# swift-nav.net
KiCad netlist of a schematic drawn in EAGLE
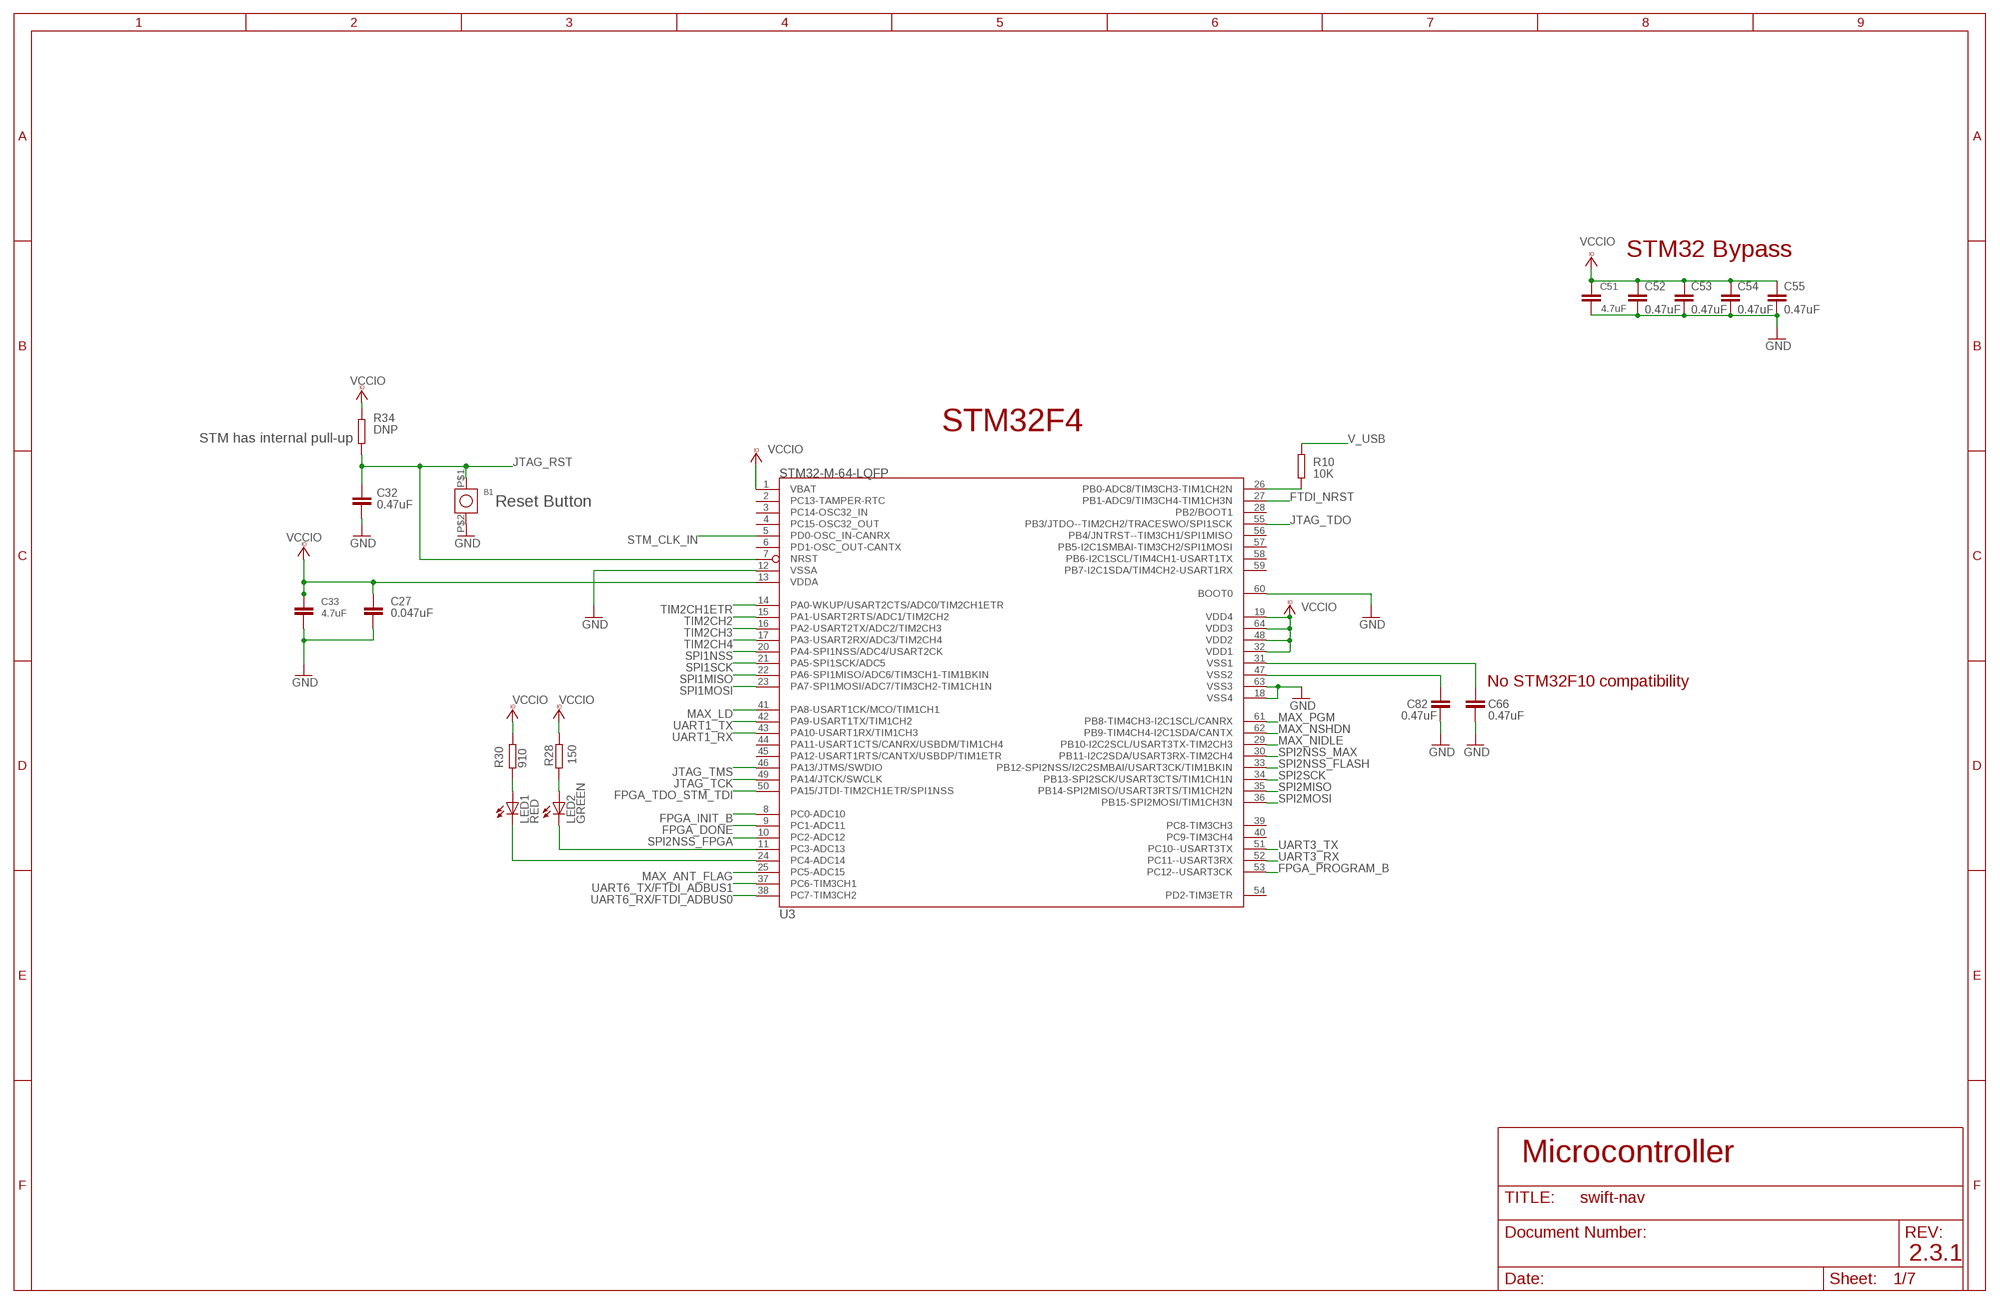
[diagram p0: schematic, sheet 1]
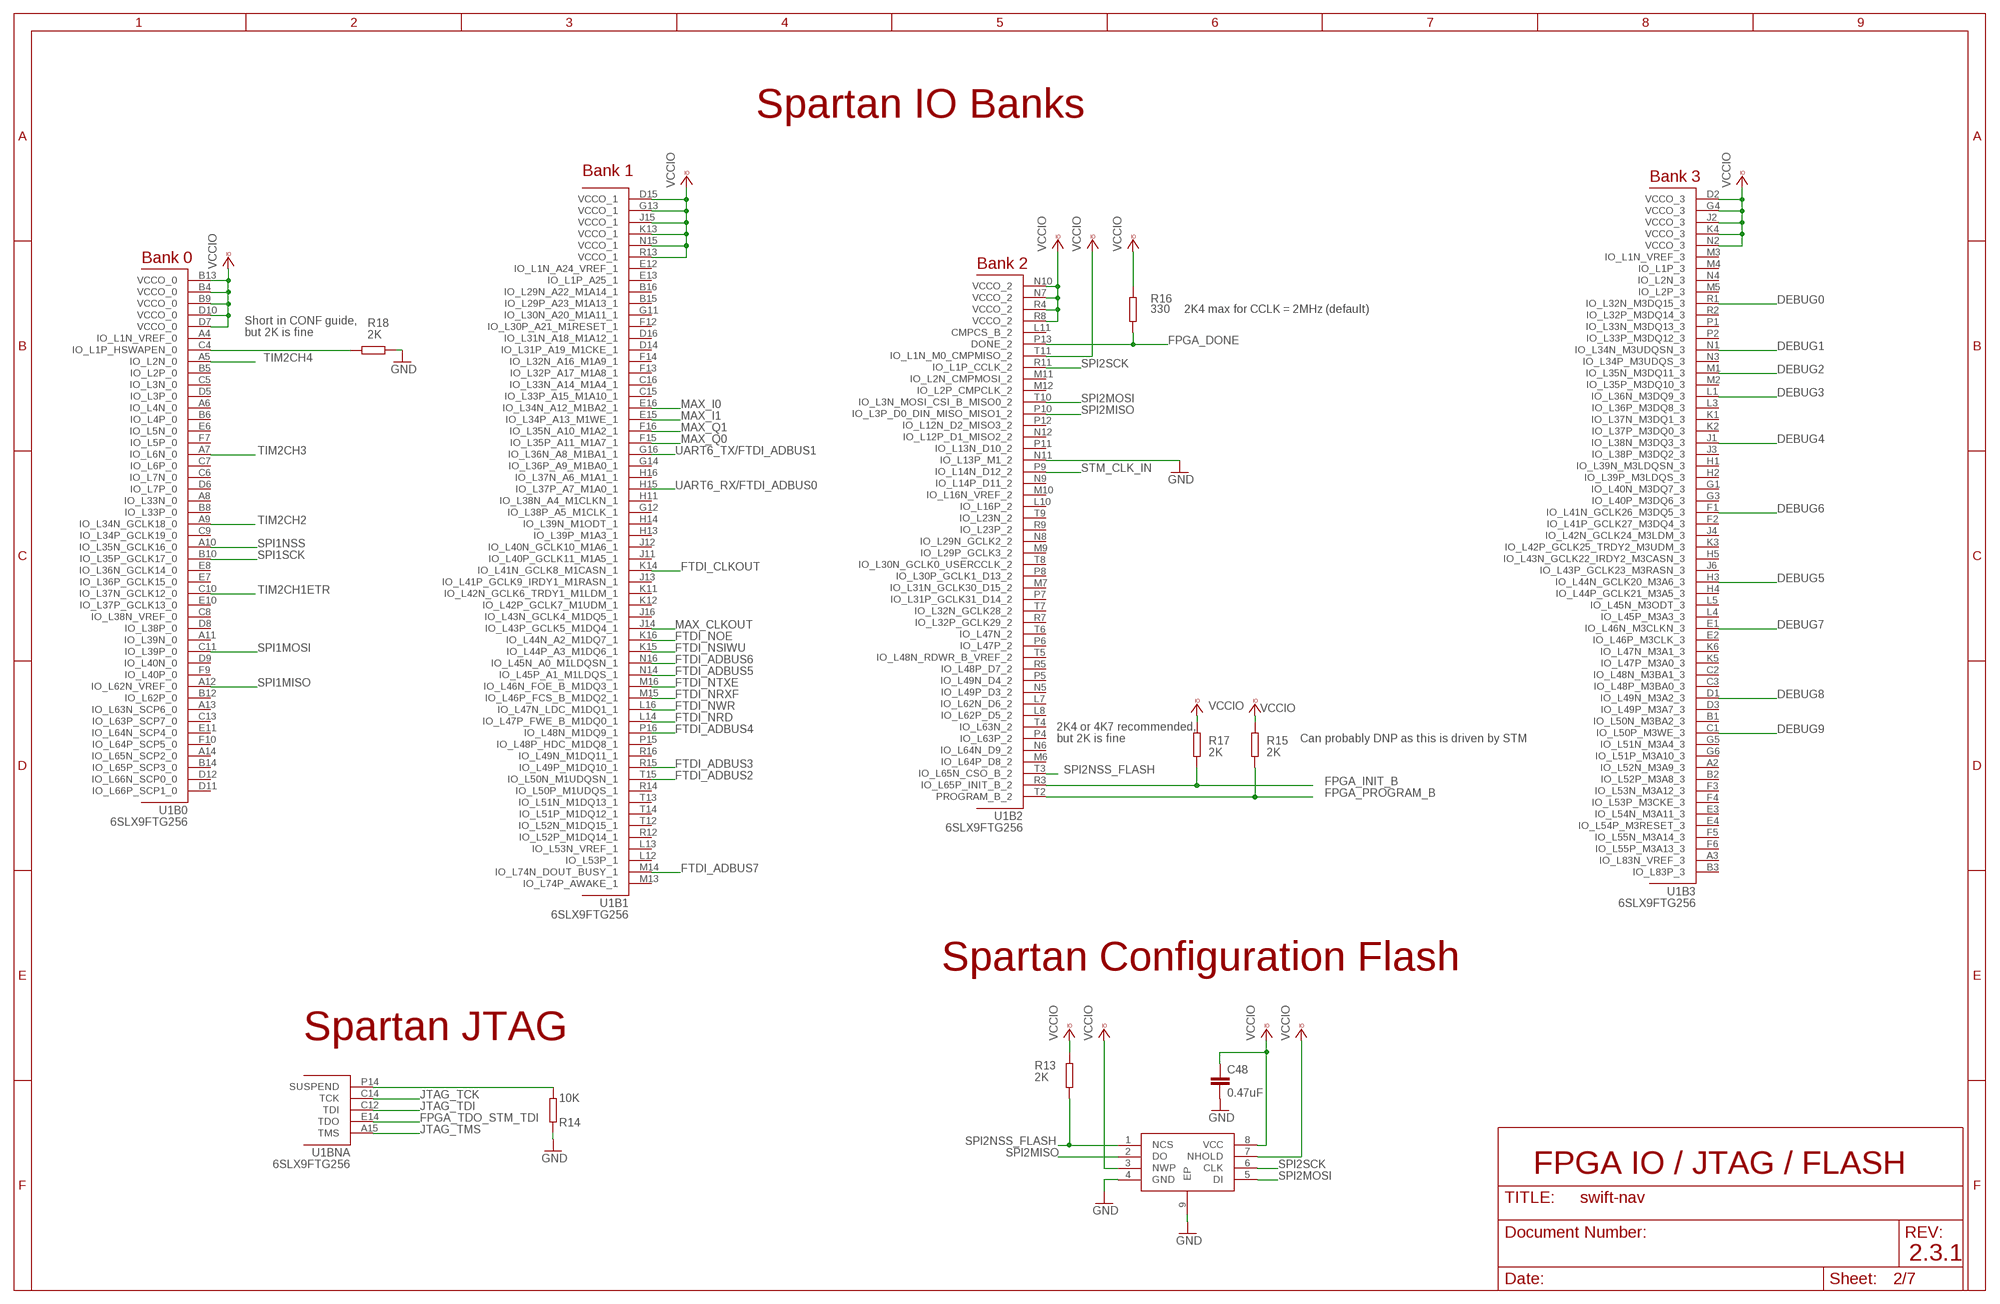
[diagram p1: schematic, sheet 2]
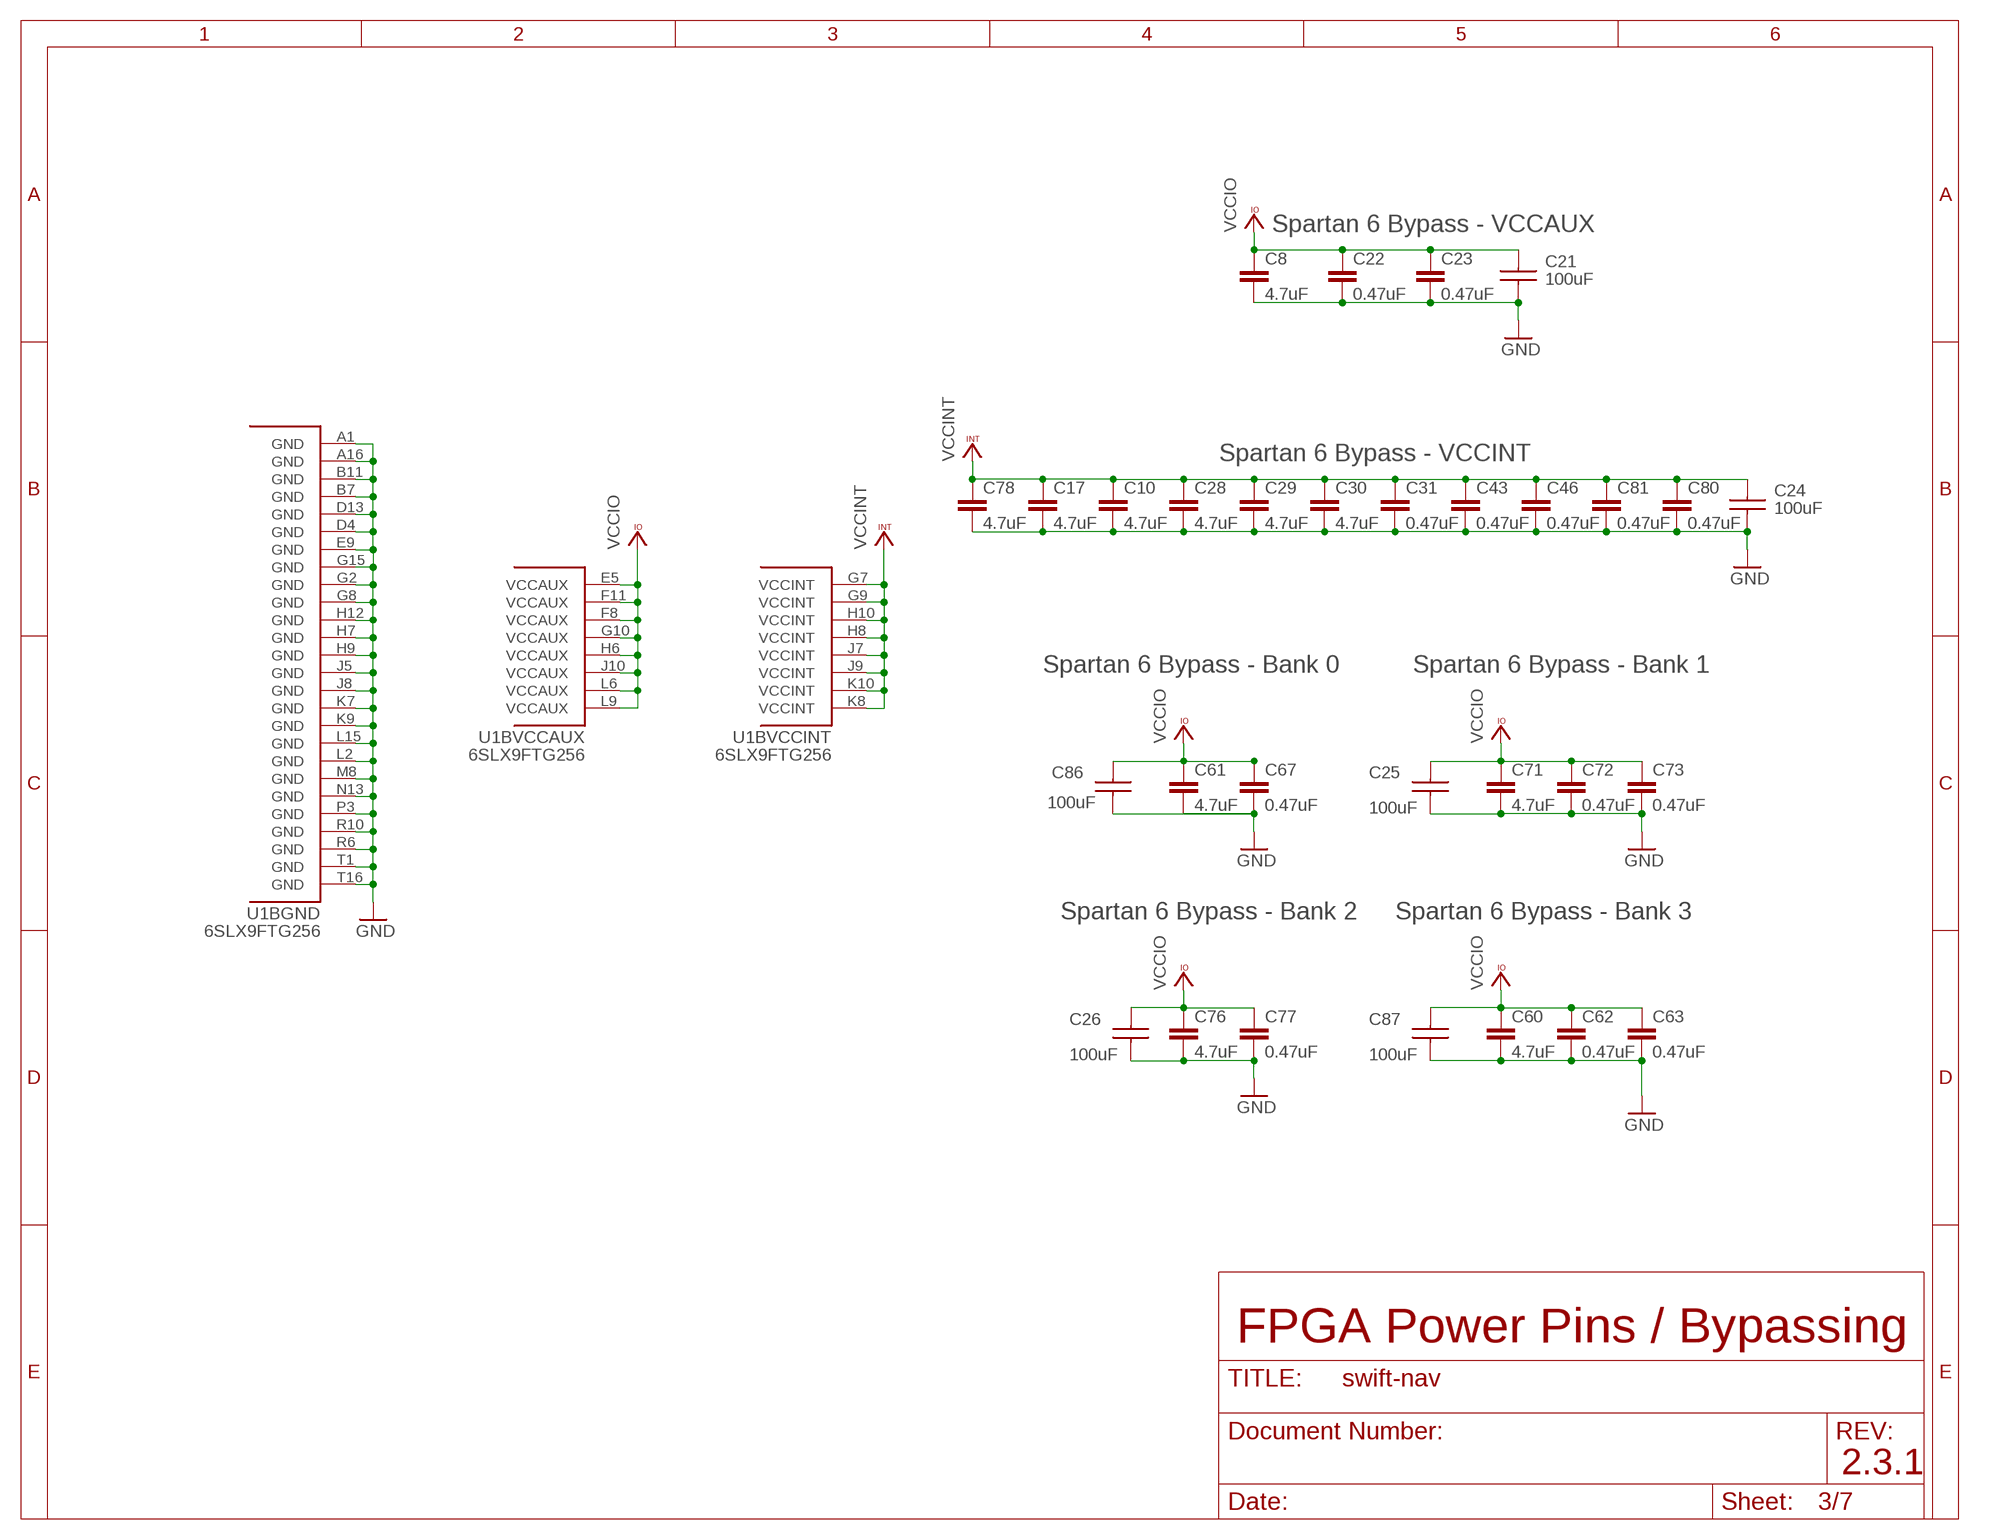
[diagram p2: schematic, sheet 3]
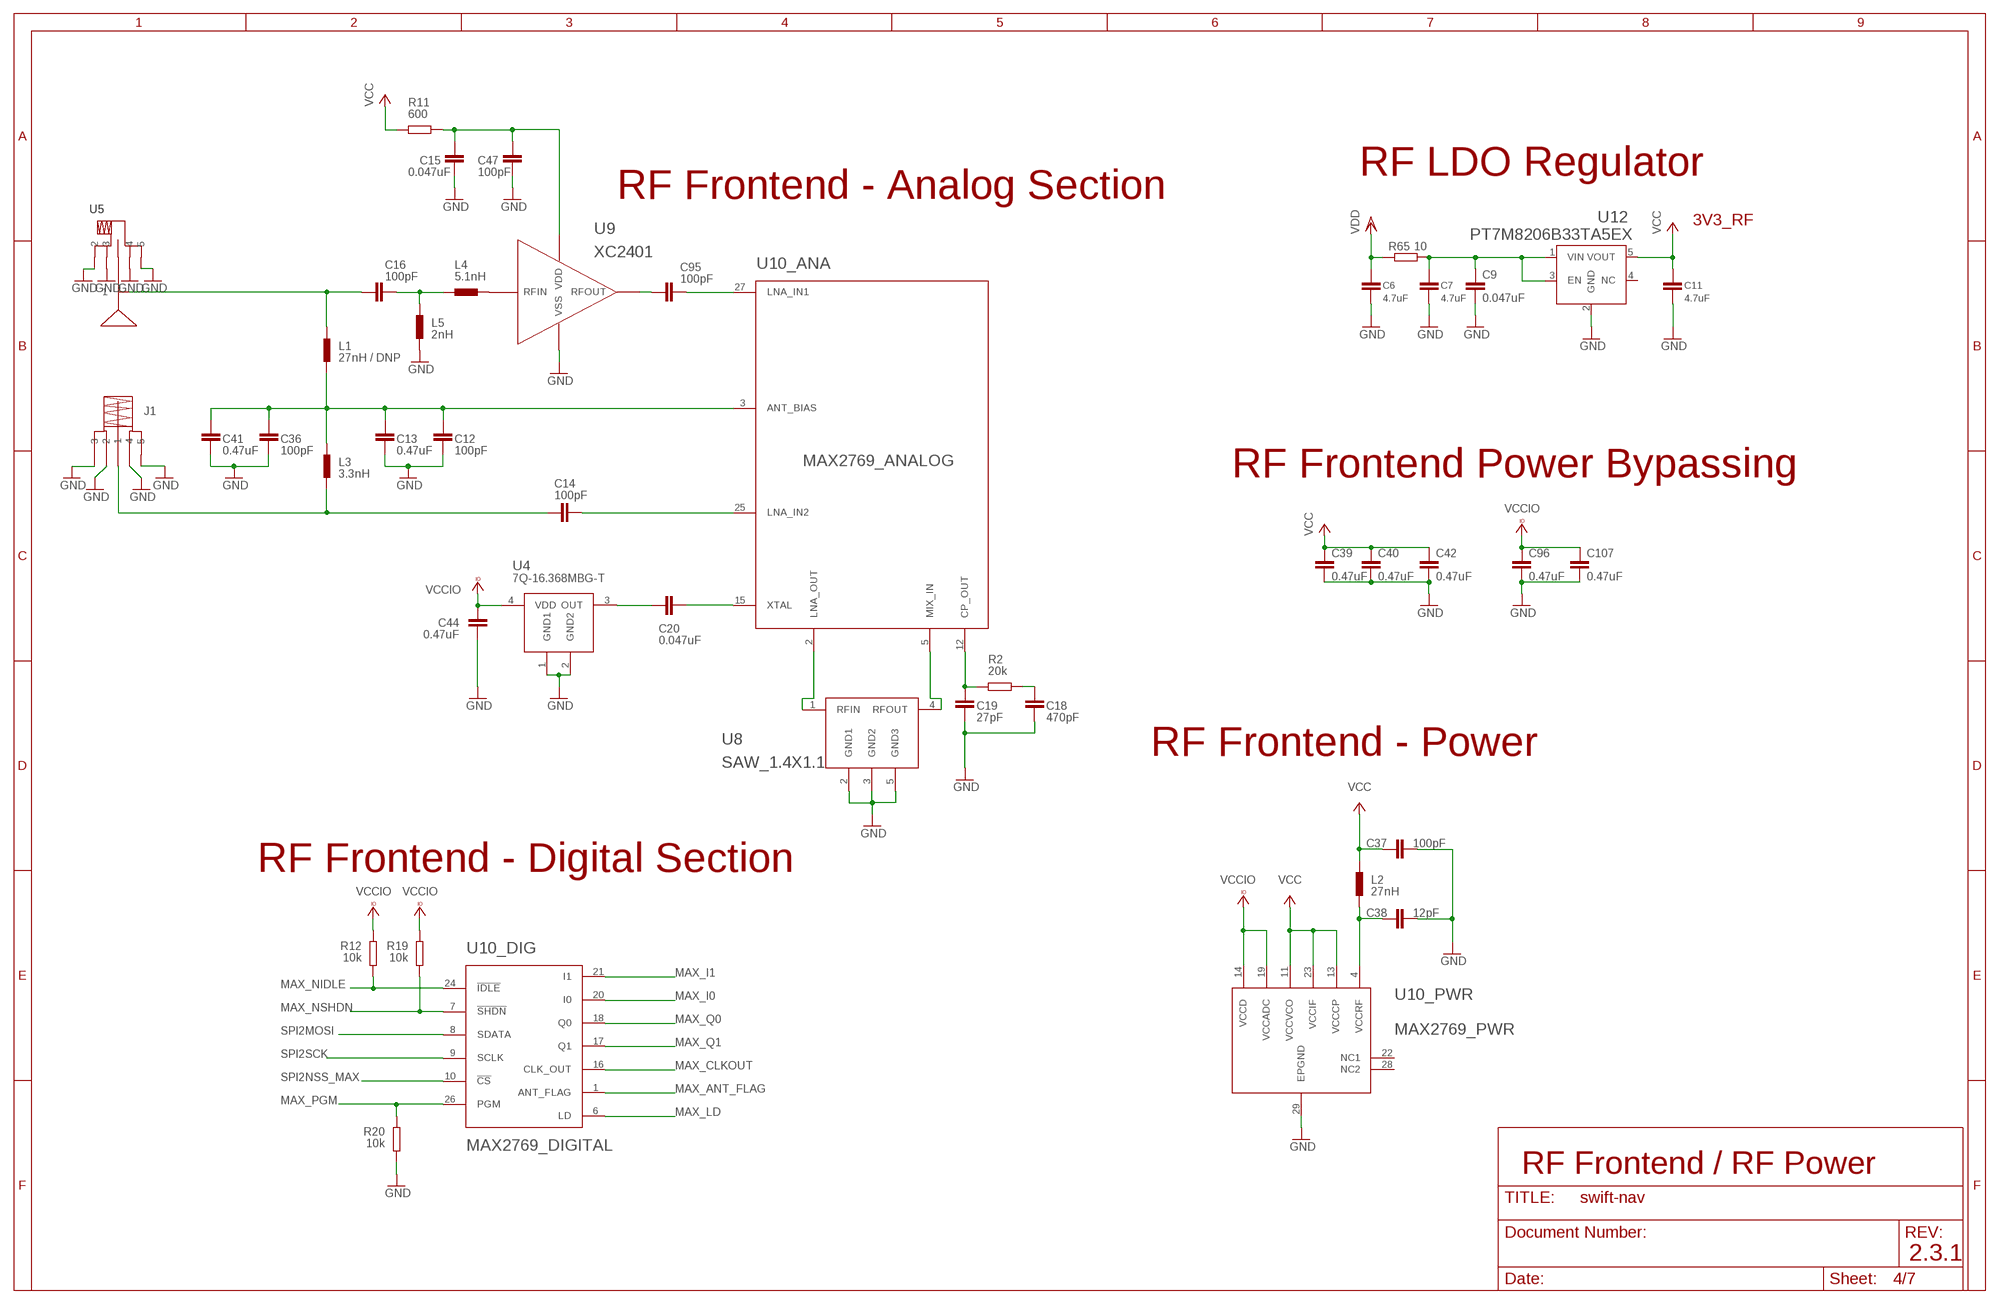
[diagram p3: schematic, sheet 4]
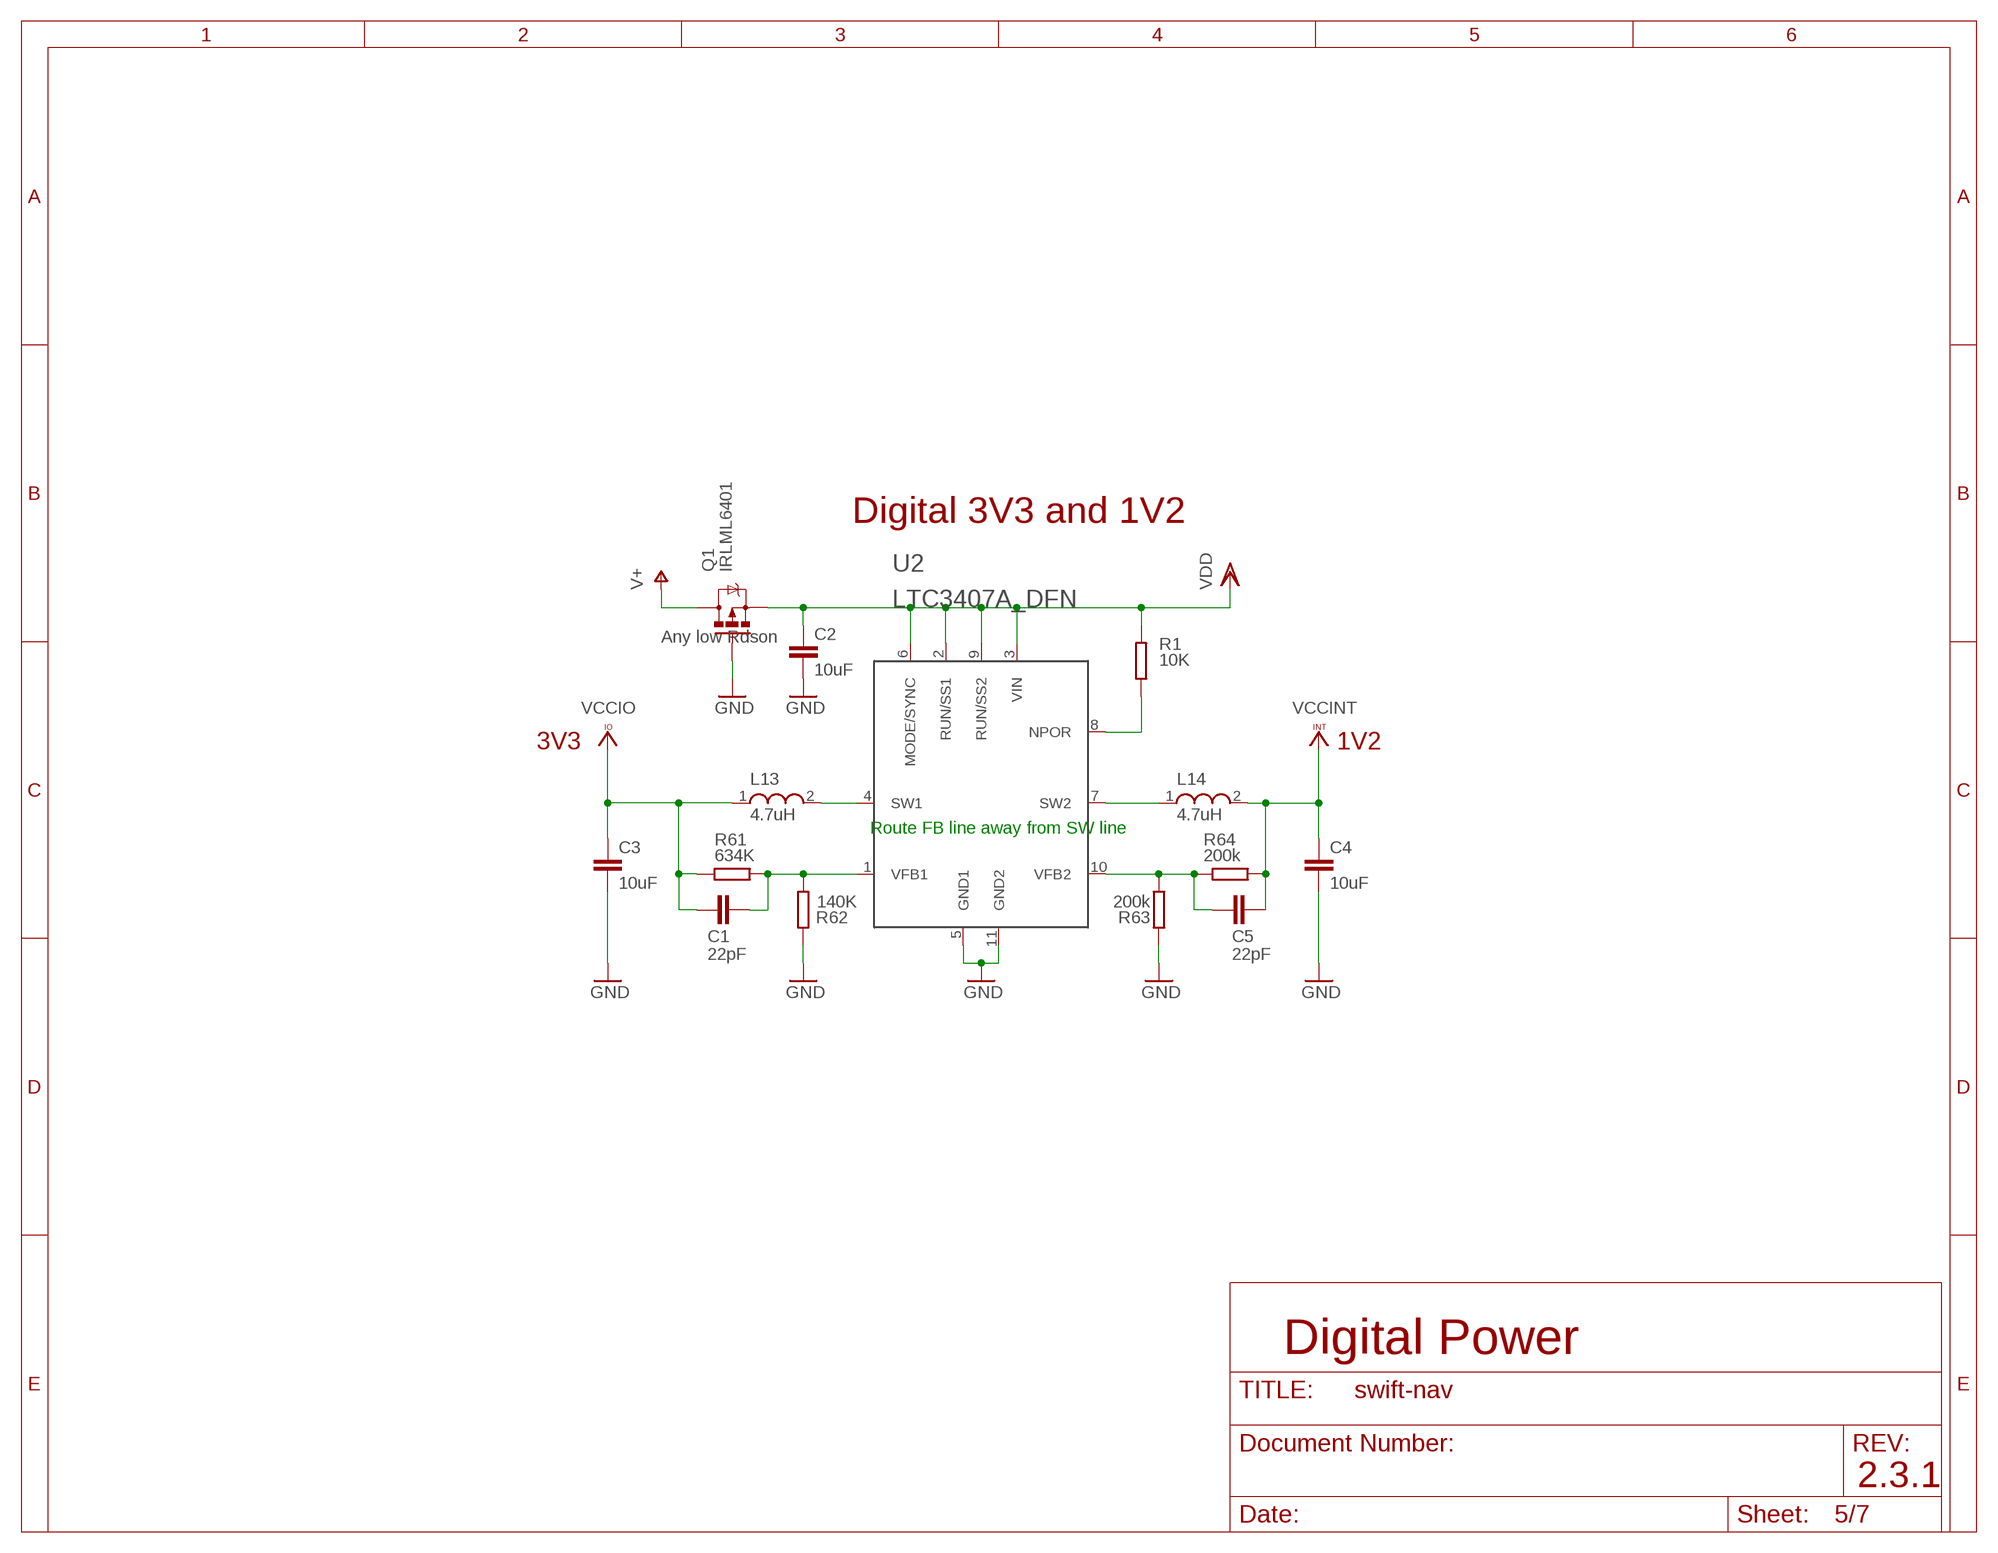
[diagram p4: schematic, sheet 5]
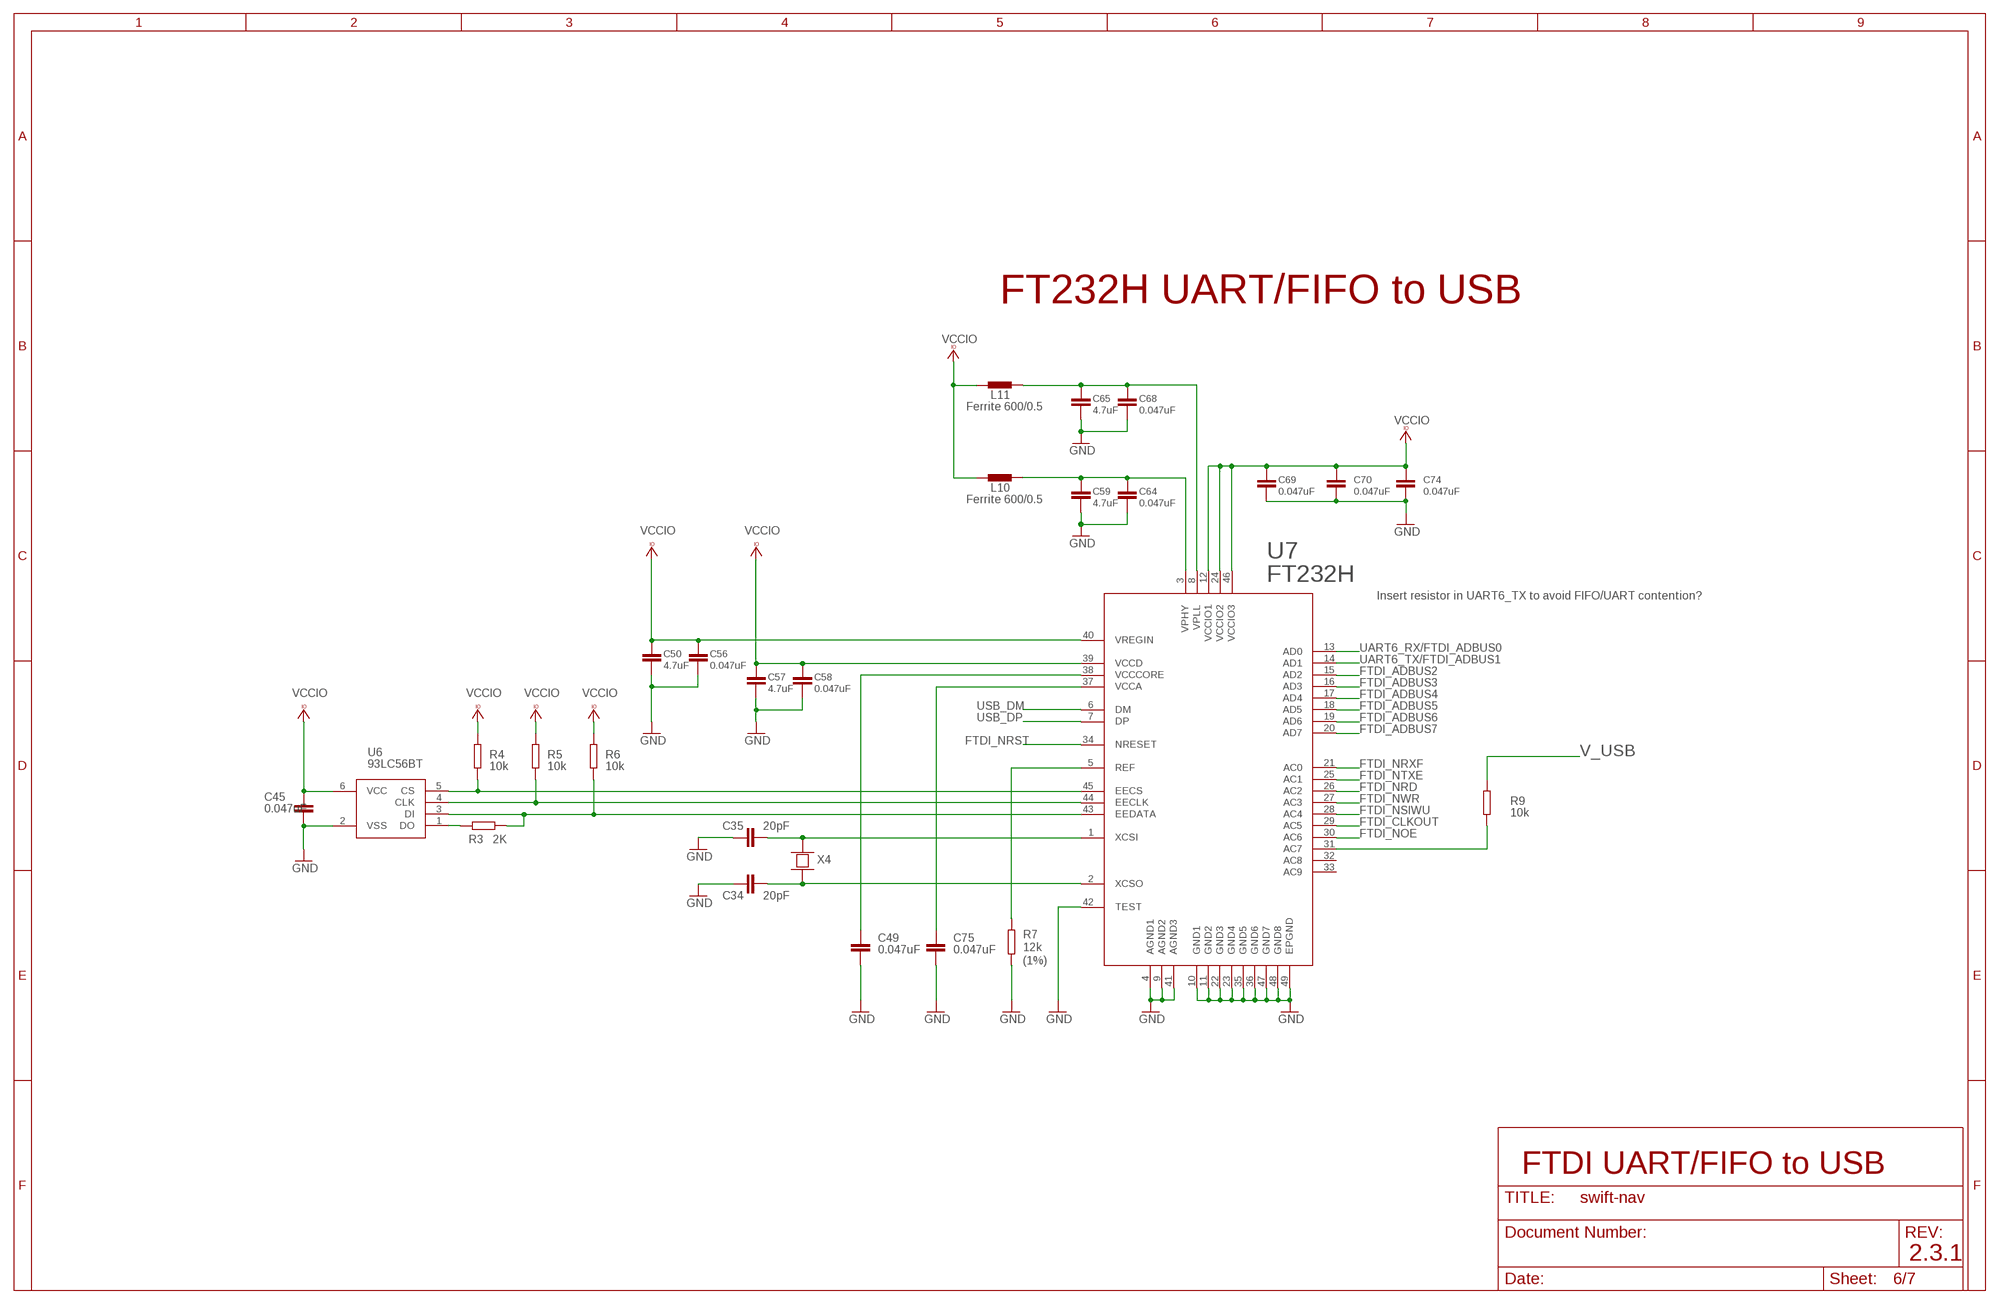
[diagram p5: schematic, sheet 6]
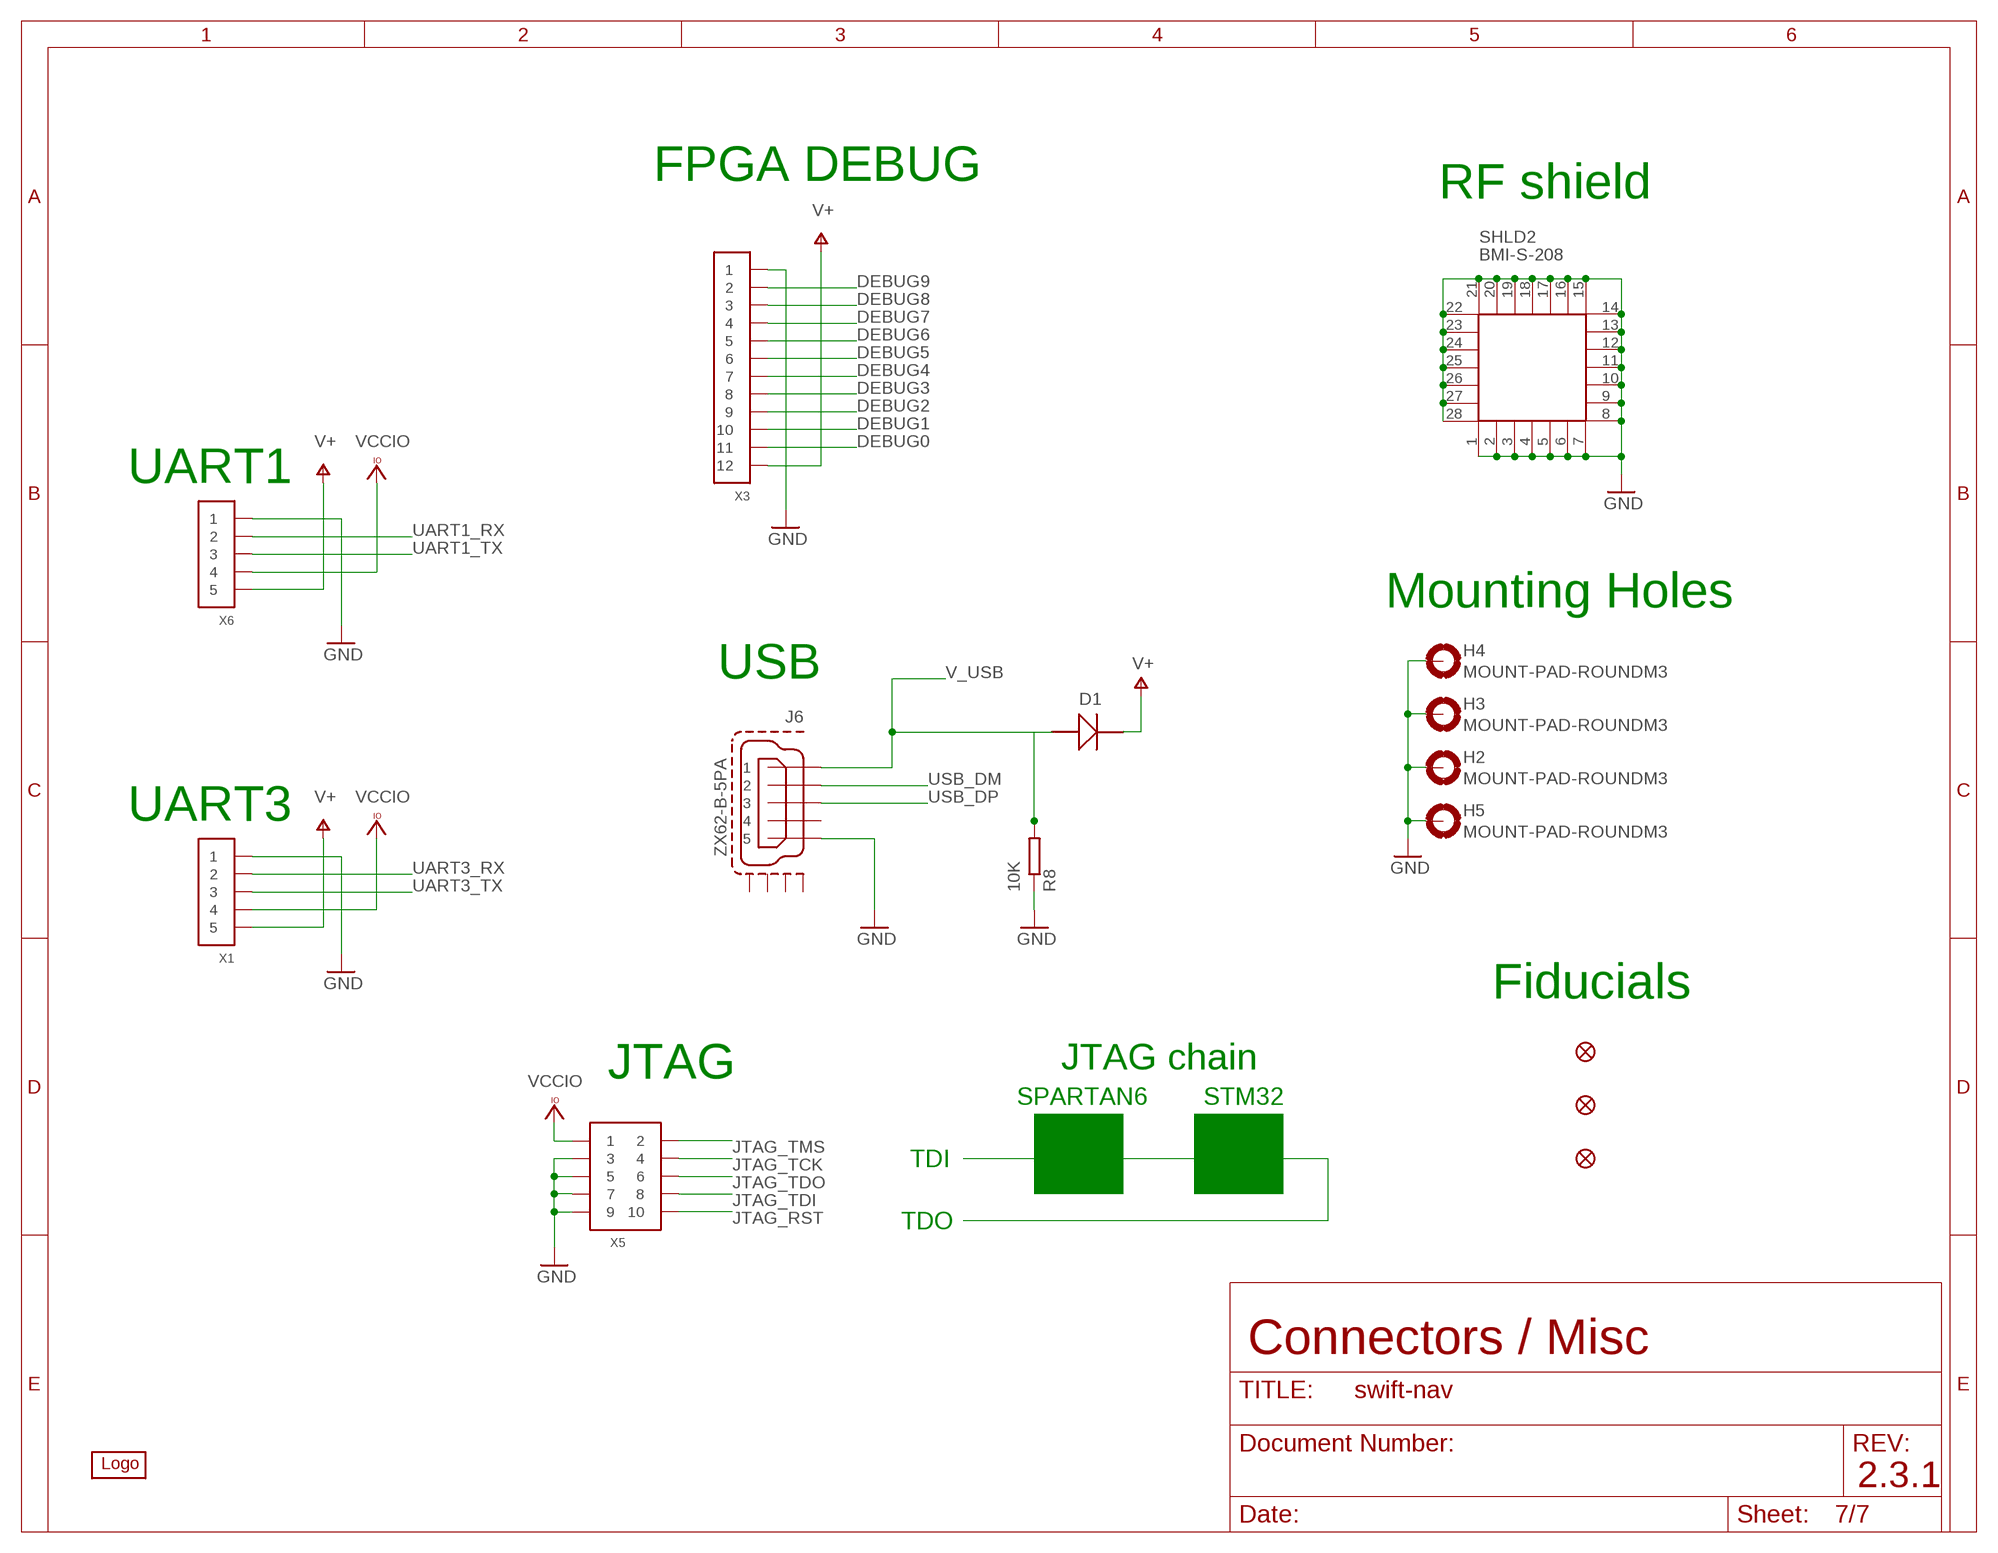
[diagram p6: schematic, sheet 7]

(export (version "E")
  (design (tool "Eeschema 10.0.6"))
  (components
    (comp (ref "C1")
      (value "22pF")
      (footprint "eagle-import:0402-CAP")
      (libsource (lib "eagle-import") (part "CAPACITOR-0402"))
    )
    (comp (ref "C2")
      (value "10uF")
      (footprint "eagle-import:1206-CAP")
      (libsource (lib "eagle-import") (part "CAPACITOR-1206"))
    )
    (comp (ref "C3")
      (value "10uF")
      (footprint "eagle-import:1206-CAP")
      (libsource (lib "eagle-import") (part "CAPACITOR-1206"))
    )
    (comp (ref "C4")
      (value "10uF")
      (footprint "eagle-import:1206-CAP")
      (libsource (lib "eagle-import") (part "CAPACITOR-1206"))
    )
    (comp (ref "C5")
      (value "22pF")
      (footprint "eagle-import:0402-CAP")
      (libsource (lib "eagle-import") (part "CAPACITOR-0402"))
    )
    (comp (ref "L13")
      (value "4.7uH")
      (footprint "eagle-import:LQM2HPN4R7MG0L")
      (libsource (lib "eagle-import") (part "LQM2HPN4R7MG0L"))
    )
    (comp (ref "L14")
      (value "4.7uH")
      (footprint "eagle-import:LQM2HPN4R7MG0L")
      (libsource (lib "eagle-import") (part "LQM2HPN4R7MG0L"))
    )
    (comp (ref "Q1")
      (value "IRLML6401")
      (footprint "eagle-import:SOT23-3")
      (libsource (lib "eagle-import") (part "MOSFET-PCHANNELSMD"))
    )
    (comp (ref "R1")
      (value "10K")
      (footprint "eagle-import:0402-RES")
      (libsource (lib "eagle-import") (part "RESISTOR-0402"))
    )
    (comp (ref "R61")
      (value "634K")
      (footprint "eagle-import:0402-RES")
      (libsource (lib "eagle-import") (part "RESISTOR-0402"))
    )
    (comp (ref "R62")
      (value "140K")
      (footprint "eagle-import:0402-RES")
      (libsource (lib "eagle-import") (part "RESISTOR-0402"))
    )
    (comp (ref "R63")
      (value "200k")
      (footprint "eagle-import:0402-RES")
      (libsource (lib "eagle-import") (part "RESISTOR-0402"))
    )
    (comp (ref "R64")
      (value "200k")
      (footprint "eagle-import:0402-RES")
      (libsource (lib "eagle-import") (part "RESISTOR-0402"))
    )
    (comp (ref "U2")
      (value "LTC3407A_DFN")
      (footprint "eagle-import:DFN10")
      (libsource (lib "eagle-import") (part "LTC3407A_DFN"))
    )
    (comp (ref "C34")
      (value "20pF")
      (footprint "eagle-import:0402-CAP")
      (libsource (lib "eagle-import") (part "CAPACITOR-0402"))
    )
    (comp (ref "C35")
      (value "20pF")
      (footprint "eagle-import:0402-CAP")
      (libsource (lib "eagle-import") (part "CAPACITOR-0402"))
    )
    (comp (ref "C45")
      (value "0.047uF")
      (footprint "eagle-import:C0402")
      (libsource (lib "eagle-import") (part "C-EUC0402"))
    )
    (comp (ref "C49")
      (value "0.047uF")
      (footprint "eagle-import:0402-CAP")
      (libsource (lib "eagle-import") (part "CAPACITOR-0402"))
    )
    (comp (ref "C50")
      (value "4.7uF")
      (footprint "eagle-import:0603-CAP")
      (libsource (lib "eagle-import") (part "CAPACITOR-0603"))
    )
    (comp (ref "C56")
      (value "0.047uF")
      (footprint "eagle-import:0402-CAP")
      (libsource (lib "eagle-import") (part "CAPACITOR-0402"))
    )
    (comp (ref "C57")
      (value "4.7uF")
      (footprint "eagle-import:0603-CAP")
      (libsource (lib "eagle-import") (part "CAPACITOR-0603"))
    )
    (comp (ref "C58")
      (value "0.047uF")
      (footprint "eagle-import:0402-CAP")
      (libsource (lib "eagle-import") (part "CAPACITOR-0402"))
    )
    (comp (ref "C59")
      (value "4.7uF")
      (footprint "eagle-import:0603-CAP")
      (libsource (lib "eagle-import") (part "CAPACITOR-0603"))
    )
    (comp (ref "C64")
      (value "0.047uF")
      (footprint "eagle-import:0402-CAP")
      (libsource (lib "eagle-import") (part "CAPACITOR-0402"))
    )
    (comp (ref "C65")
      (value "4.7uF")
      (footprint "eagle-import:0603-CAP")
      (libsource (lib "eagle-import") (part "CAPACITOR-0603"))
    )
    (comp (ref "C68")
      (value "0.047uF")
      (footprint "eagle-import:0402-CAP")
      (libsource (lib "eagle-import") (part "CAPACITOR-0402"))
    )
    (comp (ref "C69")
      (value "0.047uF")
      (footprint "eagle-import:C0603")
      (libsource (lib "eagle-import") (part "C-EUC0603"))
    )
    (comp (ref "C70")
      (value "0.047uF")
      (footprint "eagle-import:0402-CAP")
      (libsource (lib "eagle-import") (part "CAPACITOR-0402"))
    )
    (comp (ref "C74")
      (value "0.047uF")
      (footprint "eagle-import:0402-CAP")
      (libsource (lib "eagle-import") (part "CAPACITOR-0402"))
    )
    (comp (ref "C75")
      (value "0.047uF")
      (footprint "eagle-import:0402-CAP")
      (libsource (lib "eagle-import") (part "CAPACITOR-0402"))
    )
    (comp (ref "L10")
      (value "Ferrite 600/0.5")
      (footprint "eagle-import:0805-IND")
      (libsource (lib "eagle-import") (part "INDUCTOR-0805"))
    )
    (comp (ref "L11")
      (value "Ferrite 600/0.5")
      (footprint "eagle-import:0805-IND")
      (libsource (lib "eagle-import") (part "INDUCTOR-0805"))
    )
    (comp (ref "R3")
      (value "2K")
      (footprint "eagle-import:0402-RES")
      (libsource (lib "eagle-import") (part "RESISTOR-0402"))
    )
    (comp (ref "R4")
      (value "10k")
      (footprint "eagle-import:0402-RES")
      (libsource (lib "eagle-import") (part "RESISTOR-0402"))
    )
    (comp (ref "R5")
      (value "10k")
      (footprint "eagle-import:0402-RES")
      (libsource (lib "eagle-import") (part "RESISTOR-0402"))
    )
    (comp (ref "R6")
      (value "10k")
      (footprint "eagle-import:0402-RES")
      (libsource (lib "eagle-import") (part "RESISTOR-0402"))
    )
    (comp (ref "R7")
      (value "12k")
      (footprint "eagle-import:0402-RES")
      (libsource (lib "eagle-import") (part "RESISTOR-0402"))
    )
    (comp (ref "R9")
      (value "10k")
      (footprint "eagle-import:0402-RES")
      (libsource (lib "eagle-import") (part "RESISTOR-0402"))
    )
    (comp (ref "U6")
      (value "93LC56BT-I/OT")
      (footprint "eagle-import:93AA56BT-I_OT")
      (libsource (lib "eagle-import") (part "93LC56BT-I/OT"))
    )
    (comp (ref "U7")
      (value "FT232HQ")
      (footprint "eagle-import:FT232HQ")
      (libsource (lib "eagle-import") (part "FT232HQ"))
    )
    (comp (ref "X4")
      (value "NX5032GA-12M")
      (footprint "eagle-import:NX5032GA")
      (libsource (lib "eagle-import") (part "NX5032GA-12M"))
    )
    (comp (ref "C8")
      (value "4.7uF")
      (footprint "eagle-import:0603-CAP")
      (libsource (lib "eagle-import") (part "CAPACITOR-0603"))
    )
    (comp (ref "C10")
      (value "4.7uF")
      (footprint "eagle-import:0603-CAP")
      (libsource (lib "eagle-import") (part "CAPACITOR-0603"))
    )
    (comp (ref "C17")
      (value "4.7uF")
      (footprint "eagle-import:0603-CAP")
      (libsource (lib "eagle-import") (part "CAPACITOR-0603"))
    )
    (comp (ref "C21")
      (value "100uF")
      (footprint "eagle-import:C1210")
      (libsource (lib "eagle-import") (part "C1210"))
    )
    (comp (ref "C22")
      (value "0.47uF")
      (footprint "eagle-import:0402-CAP")
      (libsource (lib "eagle-import") (part "CAPACITOR-0402"))
    )
    (comp (ref "C23")
      (value "0.47uF")
      (footprint "eagle-import:0402-CAP")
      (libsource (lib "eagle-import") (part "CAPACITOR-0402"))
    )
    (comp (ref "C24")
      (value "100uF")
      (footprint "eagle-import:C1210")
      (libsource (lib "eagle-import") (part "C1210"))
    )
    (comp (ref "C25")
      (value "100uF")
      (footprint "eagle-import:C1210")
      (libsource (lib "eagle-import") (part "C1210"))
    )
    (comp (ref "C26")
      (value "100uF")
      (footprint "eagle-import:C1210")
      (libsource (lib "eagle-import") (part "C1210"))
    )
    (comp (ref "C28")
      (value "4.7uF")
      (footprint "eagle-import:0603-CAP")
      (libsource (lib "eagle-import") (part "CAPACITOR-0603"))
    )
    (comp (ref "C29")
      (value "4.7uF")
      (footprint "eagle-import:0603-CAP")
      (libsource (lib "eagle-import") (part "CAPACITOR-0603"))
    )
    (comp (ref "C30")
      (value "4.7uF")
      (footprint "eagle-import:0603-CAP")
      (libsource (lib "eagle-import") (part "CAPACITOR-0603"))
    )
    (comp (ref "C31")
      (value "0.47uF")
      (footprint "eagle-import:0402-CAP")
      (libsource (lib "eagle-import") (part "CAPACITOR-0402"))
    )
    (comp (ref "C43")
      (value "0.47uF")
      (footprint "eagle-import:0402-CAP")
      (libsource (lib "eagle-import") (part "CAPACITOR-0402"))
    )
    (comp (ref "C46")
      (value "0.47uF")
      (footprint "eagle-import:0402-CAP")
      (libsource (lib "eagle-import") (part "CAPACITOR-0402"))
    )
    (comp (ref "C60")
      (value "4.7uF")
      (footprint "eagle-import:0603-CAP")
      (libsource (lib "eagle-import") (part "CAPACITOR-0603"))
    )
    (comp (ref "C61")
      (value "4.7uF")
      (footprint "eagle-import:0603-CAP")
      (libsource (lib "eagle-import") (part "CAPACITOR-0603"))
    )
    (comp (ref "C62")
      (value "0.47uF")
      (footprint "eagle-import:0402-CAP")
      (libsource (lib "eagle-import") (part "CAPACITOR-0402"))
    )
    (comp (ref "C63")
      (value "0.47uF")
      (footprint "eagle-import:0402-CAP")
      (libsource (lib "eagle-import") (part "CAPACITOR-0402"))
    )
    (comp (ref "C67")
      (value "0.47uF")
      (footprint "eagle-import:0402-CAP")
      (libsource (lib "eagle-import") (part "CAPACITOR-0402"))
    )
    (comp (ref "C71")
      (value "4.7uF")
      (footprint "eagle-import:0603-CAP")
      (libsource (lib "eagle-import") (part "CAPACITOR-0603"))
    )
    (comp (ref "C72")
      (value "0.47uF")
      (footprint "eagle-import:0402-CAP")
      (libsource (lib "eagle-import") (part "CAPACITOR-0402"))
    )
    (comp (ref "C73")
      (value "0.47uF")
      (footprint "eagle-import:0402-CAP")
      (libsource (lib "eagle-import") (part "CAPACITOR-0402"))
    )
    (comp (ref "C76")
      (value "4.7uF")
      (footprint "eagle-import:0603-CAP")
      (libsource (lib "eagle-import") (part "CAPACITOR-0603"))
    )
    (comp (ref "C77")
      (value "0.47uF")
      (footprint "eagle-import:0402-CAP")
      (libsource (lib "eagle-import") (part "CAPACITOR-0402"))
    )
    (comp (ref "C78")
      (value "4.7uF")
      (footprint "eagle-import:0603-CAP")
      (libsource (lib "eagle-import") (part "CAPACITOR-0603"))
    )
    (comp (ref "C80")
      (value "0.47uF")
      (footprint "eagle-import:0402-CAP")
      (libsource (lib "eagle-import") (part "CAPACITOR-0402"))
    )
    (comp (ref "C81")
      (value "0.47uF")
      (footprint "eagle-import:0402-CAP")
      (libsource (lib "eagle-import") (part "CAPACITOR-0402"))
    )
    (comp (ref "C86")
      (value "100uF")
      (footprint "eagle-import:C1210")
      (libsource (lib "eagle-import") (part "C1210"))
    )
    (comp (ref "C87")
      (value "100uF")
      (footprint "eagle-import:C1210")
      (libsource (lib "eagle-import") (part "C1210"))
    )
    (comp (ref "U1")
      (value "6SLX9FTG256")
      (footprint "eagle-import:FT256")
      (libsource (lib "eagle-import") (part "6SLX9FTG256"))
    )
    (comp (ref "D1")
      (value "MBR0520")
      (footprint "eagle-import:SOD-123")
      (libsource (lib "eagle-import") (part "MBR0520"))
    )
    (comp (ref "H2")
      (value "MOUNT-PAD-ROUNDM3")
      (footprint "eagle-import:M3-PAD")
      (libsource (lib "eagle-import") (part "MOUNT-PAD-ROUNDM3"))
    )
    (comp (ref "H3")
      (value "MOUNT-PAD-ROUNDM3")
      (footprint "eagle-import:M3-PAD")
      (libsource (lib "eagle-import") (part "MOUNT-PAD-ROUNDM3"))
    )
    (comp (ref "H4")
      (value "MOUNT-PAD-ROUNDM3")
      (footprint "eagle-import:M3-PAD")
      (libsource (lib "eagle-import") (part "MOUNT-PAD-ROUNDM3"))
    )
    (comp (ref "H5")
      (value "MOUNT-PAD-ROUNDM3")
      (footprint "eagle-import:M3-PAD")
      (libsource (lib "eagle-import") (part "MOUNT-PAD-ROUNDM3"))
    )
    (comp (ref "J6")
      (value "ZX62-B-5PA")
      (footprint "eagle-import:ZX62-B-5PA")
      (libsource (lib "eagle-import") (part "ZX62-B-5PA"))
    )
    (comp (ref "JP8")
      (value "FIDUCIAL1.5X3")
      (footprint "eagle-import:FIDUCIAL-1.5X3")
      (libsource (lib "eagle-import") (part "FIDUCIAL1.5X3"))
    )
    (comp (ref "JP9")
      (value "FIDUCIAL1.5X3")
      (footprint "eagle-import:FIDUCIAL-1.5X3")
      (libsource (lib "eagle-import") (part "FIDUCIAL1.5X3"))
    )
    (comp (ref "JP10")
      (value "FIDUCIAL1.5X3")
      (footprint "eagle-import:FIDUCIAL-1.5X3")
      (libsource (lib "eagle-import") (part "FIDUCIAL1.5X3"))
    )
    (comp (ref "R8")
      (value "10K")
      (footprint "eagle-import:0402-RES")
      (libsource (lib "eagle-import") (part "RESISTOR-0402"))
    )
    (comp (ref "SHLD2")
      (value "BMI-S-208")
      (footprint "eagle-import:BMI-S-208")
      (libsource (lib "eagle-import") (part "BMI-S-208"))
    )
    (comp (ref "U$2")
      (value "LOGOLOGO3_SMALL")
      (footprint "eagle-import:LOGO3_SMALL")
      (libsource (lib "eagle-import") (part "LOGOLOGO3_SMALL"))
    )
    (comp (ref "X1")
      (value "CONN_5-1-53261")
      (footprint "eagle-import:PB-53261-05")
      (libsource (lib "eagle-import") (part "CONN_5-1-53261"))
    )
    (comp (ref "X3")
      (value "FPGA DEBUG")
      (footprint "eagle-import:PB-53261-12")
      (libsource (lib "eagle-import") (part "CONN_12-1-53261"))
    )
    (comp (ref "X5")
      (value "CONN_5-2")
      (footprint "eagle-import:FTSH-105-D")
      (libsource (lib "eagle-import") (part "CONN_5-2"))
    )
    (comp (ref "X6")
      (value "CONN_5-1-53261")
      (footprint "eagle-import:PB-53261-05")
      (libsource (lib "eagle-import") (part "CONN_5-1-53261"))
    )
    (comp (ref "B1")
      (value "B3U-1000P")
      (footprint "eagle-import:B3U-1000P")
      (libsource (lib "eagle-import") (part "B3U-1000P"))
    )
    (comp (ref "C27")
      (value "0.047uF")
      (footprint "eagle-import:0402-CAP")
      (libsource (lib "eagle-import") (part "CAPACITOR-0402"))
    )
    (comp (ref "C32")
      (value "0.47uF")
      (footprint "eagle-import:0402-CAP")
      (libsource (lib "eagle-import") (part "CAPACITOR-0402"))
    )
    (comp (ref "C33")
      (value "4.7uF")
      (footprint "eagle-import:0603-CAP")
      (libsource (lib "eagle-import") (part "CAPACITOR-0603"))
    )
    (comp (ref "C51")
      (value "4.7uF")
      (footprint "eagle-import:0603-CAP")
      (libsource (lib "eagle-import") (part "CAPACITOR-0603"))
    )
    (comp (ref "C52")
      (value "0.47uF")
      (footprint "eagle-import:0402-CAP")
      (libsource (lib "eagle-import") (part "CAPACITOR-0402"))
    )
    (comp (ref "C53")
      (value "0.47uF")
      (footprint "eagle-import:0402-CAP")
      (libsource (lib "eagle-import") (part "CAPACITOR-0402"))
    )
    (comp (ref "C54")
      (value "0.47uF")
      (footprint "eagle-import:0402-CAP")
      (libsource (lib "eagle-import") (part "CAPACITOR-0402"))
    )
    (comp (ref "C55")
      (value "0.47uF")
      (footprint "eagle-import:0402-CAP")
      (libsource (lib "eagle-import") (part "CAPACITOR-0402"))
    )
    (comp (ref "C66")
      (value "0.47uF")
      (footprint "eagle-import:0402-CAP")
      (libsource (lib "eagle-import") (part "CAPACITOR-0402"))
    )
    (comp (ref "C82")
      (value "0.47uF")
      (footprint "eagle-import:0402-CAP")
      (libsource (lib "eagle-import") (part "CAPACITOR-0402"))
    )
    (comp (ref "LED1")
      (value "RED")
      (footprint "eagle-import:0603-LED")
      (libsource (lib "eagle-import") (part "LED-0603"))
    )
    (comp (ref "LED2")
      (value "GREEN")
      (footprint "eagle-import:0603-LED")
      (libsource (lib "eagle-import") (part "LED-0603"))
    )
    (comp (ref "R10")
      (value "10K")
      (footprint "eagle-import:0402-RES")
      (libsource (lib "eagle-import") (part "RESISTOR-0402"))
    )
    (comp (ref "R28")
      (value "150")
      (footprint "eagle-import:0402-RES")
      (libsource (lib "eagle-import") (part "RESISTOR-0402"))
    )
    (comp (ref "R30")
      (value "910")
      (footprint "eagle-import:0402-RES")
      (libsource (lib "eagle-import") (part "RESISTOR-0402"))
    )
    (comp (ref "R34")
      (value "DNP")
      (footprint "eagle-import:0402-RES")
      (libsource (lib "eagle-import") (part "RESISTOR-0402"))
    )
    (comp (ref "U3")
      (value "STM32-M-64-LQFP")
      (footprint "eagle-import:LQFP64")
      (libsource (lib "eagle-import") (part "STM32-M-64-LQFP"))
    )
    (comp (ref "C48")
      (value "0.47uF")
      (footprint "eagle-import:0402-CAP")
      (libsource (lib "eagle-import") (part "CAPACITOR-0402"))
    )
    (comp (ref "R13")
      (value "2K")
      (footprint "eagle-import:0402-RES")
      (libsource (lib "eagle-import") (part "RESISTOR-0402"))
    )
    (comp (ref "R14")
      (value "10K")
      (footprint "eagle-import:0402-RES")
      (libsource (lib "eagle-import") (part "RESISTOR-0402"))
    )
    (comp (ref "R15")
      (value "2K")
      (footprint "eagle-import:0402-RES")
      (libsource (lib "eagle-import") (part "RESISTOR-0402"))
    )
    (comp (ref "R16")
      (value "330")
      (footprint "eagle-import:0402-RES")
      (libsource (lib "eagle-import") (part "RESISTOR-0402"))
    )
    (comp (ref "R17")
      (value "2K")
      (footprint "eagle-import:0402-RES")
      (libsource (lib "eagle-import") (part "RESISTOR-0402"))
    )
    (comp (ref "R18")
      (value "2K")
      (footprint "eagle-import:0402-RES")
      (libsource (lib "eagle-import") (part "RESISTOR-0402"))
    )
    (comp (ref "U13")
      (value "M25PX80")
      (footprint "eagle-import:M25P80_MLP8")
      (libsource (lib "eagle-import") (part "M25P80_MLP8"))
    )
    (comp (ref "C6")
      (value "4.7uF")
      (footprint "eagle-import:0603-CAP")
      (libsource (lib "eagle-import") (part "CAPACITOR-0603"))
    )
    (comp (ref "C7")
      (value "4.7uF")
      (footprint "eagle-import:0603-CAP")
      (libsource (lib "eagle-import") (part "CAPACITOR-0603"))
    )
    (comp (ref "C9")
      (value "0.047uF")
      (footprint "eagle-import:0402-CAP")
      (libsource (lib "eagle-import") (part "CAPACITOR-0402"))
    )
    (comp (ref "C11")
      (value "4.7uF")
      (footprint "eagle-import:0603-CAP")
      (libsource (lib "eagle-import") (part "CAPACITOR-0603"))
    )
    (comp (ref "C12")
      (value "100pF")
      (footprint "eagle-import:0402-CAP")
      (libsource (lib "eagle-import") (part "CAPACITOR-0402"))
    )
    (comp (ref "C13")
      (value "0.47uF")
      (footprint "eagle-import:0402-CAP")
      (libsource (lib "eagle-import") (part "CAPACITOR-0402"))
    )
    (comp (ref "C14")
      (value "100pF")
      (footprint "eagle-import:0402-CAP")
      (libsource (lib "eagle-import") (part "CAPACITOR-0402"))
    )
    (comp (ref "C15")
      (value "0.047uF")
      (footprint "eagle-import:0402-CAP")
      (libsource (lib "eagle-import") (part "CAPACITOR-0402"))
    )
    (comp (ref "C16")
      (value "100pF")
      (footprint "eagle-import:0402-CAP")
      (libsource (lib "eagle-import") (part "CAPACITOR-0402"))
    )
    (comp (ref "C18")
      (value "470pF")
      (footprint "eagle-import:0402-CAP")
      (libsource (lib "eagle-import") (part "CAPACITOR-0402"))
    )
    (comp (ref "C19")
      (value "27pF")
      (footprint "eagle-import:0402-CAP")
      (libsource (lib "eagle-import") (part "CAPACITOR-0402"))
    )
    (comp (ref "C20")
      (value "0.047uF")
      (footprint "eagle-import:0402-CAP")
      (libsource (lib "eagle-import") (part "CAPACITOR-0402"))
    )
    (comp (ref "C36")
      (value "100pF")
      (footprint "eagle-import:0402-CAP")
      (libsource (lib "eagle-import") (part "CAPACITOR-0402"))
    )
    (comp (ref "C37")
      (value "100pF")
      (footprint "eagle-import:0402-CAP")
      (libsource (lib "eagle-import") (part "CAPACITOR-0402"))
    )
    (comp (ref "C38")
      (value "12pF")
      (footprint "eagle-import:0402-CAP")
      (libsource (lib "eagle-import") (part "CAPACITOR-0402"))
    )
    (comp (ref "C39")
      (value "0.47uF")
      (footprint "eagle-import:0402-CAP")
      (libsource (lib "eagle-import") (part "CAPACITOR-0402"))
    )
    (comp (ref "C40")
      (value "0.47uF")
      (footprint "eagle-import:0402-CAP")
      (libsource (lib "eagle-import") (part "CAPACITOR-0402"))
    )
    (comp (ref "C41")
      (value "0.47uF")
      (footprint "eagle-import:0402-CAP")
      (libsource (lib "eagle-import") (part "CAPACITOR-0402"))
    )
    (comp (ref "C42")
      (value "0.47uF")
      (footprint "eagle-import:0402-CAP")
      (libsource (lib "eagle-import") (part "CAPACITOR-0402"))
    )
    (comp (ref "C44")
      (value "0.47uF")
      (footprint "eagle-import:0402-CAP")
      (libsource (lib "eagle-import") (part "CAPACITOR-0402"))
    )
    (comp (ref "C47")
      (value "100pF")
      (footprint "eagle-import:0402-CAP")
      (libsource (lib "eagle-import") (part "CAPACITOR-0402"))
    )
    (comp (ref "C95")
      (value "100pF")
      (footprint "eagle-import:0402-CAP")
      (libsource (lib "eagle-import") (part "CAPACITOR-0402"))
    )
    (comp (ref "C96")
      (value "0.47uF")
      (footprint "eagle-import:0402-CAP")
      (libsource (lib "eagle-import") (part "CAPACITOR-0402"))
    )
    (comp (ref "C107")
      (value "0.47uF")
      (footprint "eagle-import:0402-CAP")
      (libsource (lib "eagle-import") (part "CAPACITOR-0402"))
    )
    (comp (ref "J1")
      (value "SMA_EDGE")
      (footprint "eagle-import:SMA_EDGE")
      (libsource (lib "eagle-import") (part "SMA_EDGE"))
    )
    (comp (ref "L1")
      (value "27nH / DNP")
      (footprint "eagle-import:0402-IND")
      (libsource (lib "eagle-import") (part "INDUCTOR-0402"))
    )
    (comp (ref "L2")
      (value "27nH")
      (footprint "eagle-import:0402-IND")
      (libsource (lib "eagle-import") (part "INDUCTOR-0402"))
    )
    (comp (ref "L3")
      (value "3.3nH")
      (footprint "eagle-import:0402-IND")
      (libsource (lib "eagle-import") (part "INDUCTOR-0402"))
    )
    (comp (ref "L4")
      (value "5.1nH")
      (footprint "eagle-import:0402-IND")
      (libsource (lib "eagle-import") (part "INDUCTOR-0402"))
    )
    (comp (ref "L5")
      (value "2nH")
      (footprint "eagle-import:0402-IND")
      (libsource (lib "eagle-import") (part "INDUCTOR-0402"))
    )
    (comp (ref "R2")
      (value "20k")
      (footprint "eagle-import:0402-RES")
      (libsource (lib "eagle-import") (part "RESISTOR-0402"))
    )
    (comp (ref "R11")
      (value "600")
      (footprint "eagle-import:0402-RES")
      (libsource (lib "eagle-import") (part "RESISTOR-0402"))
    )
    (comp (ref "R12")
      (value "10k")
      (footprint "eagle-import:0402-RES")
      (libsource (lib "eagle-import") (part "RESISTOR-0402"))
    )
    (comp (ref "R19")
      (value "10k")
      (footprint "eagle-import:0402-RES")
      (libsource (lib "eagle-import") (part "RESISTOR-0402"))
    )
    (comp (ref "R20")
      (value "10k")
      (footprint "eagle-import:0402-RES")
      (libsource (lib "eagle-import") (part "RESISTOR-0402"))
    )
    (comp (ref "R65")
      (value "10")
      (footprint "eagle-import:0402-RES")
      (libsource (lib "eagle-import") (part "RESISTOR-0402"))
    )
    (comp (ref "U4")
      (value "7Q-16.368MBG-T")
      (footprint "eagle-import:TCX_7Q")
      (libsource (lib "eagle-import") (part "7Q-16.368MBG-T"))
    )
    (comp (ref "U5")
      (value "SMA_PATCH_SMDGND")
      (footprint "eagle-import:SMA_PATCH_SMDGND")
      (libsource (lib "eagle-import") (part "SMA_PATCH_SMDGND"))
    )
    (comp (ref "U8")
      (value "SAW_1.4X1.1")
      (footprint "eagle-import:SAW_1.4X1.1")
      (libsource (lib "eagle-import") (part "SAW_1.4X1.1"))
    )
    (comp (ref "U9")
      (value "XC2401")
      (footprint "eagle-import:XC2401")
      (libsource (lib "eagle-import") (part "XC2401"))
    )
    (comp (ref "U10")
      (value "MAX2769")
      (footprint "eagle-import:MAX2769")
      (libsource (lib "eagle-import") (part "MAX2769"))
    )
    (comp (ref "U12")
      (value "PT7M8206B33TA5EX")
      (footprint "eagle-import:PT7M8206B33TA5EX")
      (libsource (lib "eagle-import") (part "PT7M8206B33TA5EX"))
    )
  )
  (nets
    (net (code "1") (name "DEBUG0") (class "Default")
      (node (ref "U1") (pin "R1") (pinfunction "IO_L32N_M3DQ15_3_R1") (pintype "bidirectional"))
      (node (ref "X3") (pin "11") (pinfunction "11_11") (pintype "bidirectional"))
    )
    (net (code "2") (name "DEBUG1") (class "Default")
      (node (ref "U1") (pin "N1") (pinfunction "IO_L34N_M3UDQSN_3_N1") (pintype "bidirectional"))
      (node (ref "X3") (pin "10") (pinfunction "10_10") (pintype "bidirectional"))
    )
    (net (code "3") (name "DEBUG2") (class "Default")
      (node (ref "U1") (pin "M1") (pinfunction "IO_L35N_M3DQ11_3_M1") (pintype "bidirectional"))
      (node (ref "X3") (pin "9") (pinfunction "9_9") (pintype "bidirectional"))
    )
    (net (code "4") (name "DEBUG3") (class "Default")
      (node (ref "U1") (pin "L1") (pinfunction "IO_L36N_M3DQ9_3_L1") (pintype "bidirectional"))
      (node (ref "X3") (pin "8") (pinfunction "8_8") (pintype "bidirectional"))
    )
    (net (code "5") (name "DEBUG4") (class "Default")
      (node (ref "U1") (pin "J1") (pinfunction "IO_L38N_M3DQ3_3_J1") (pintype "bidirectional"))
      (node (ref "X3") (pin "7") (pinfunction "7_7") (pintype "bidirectional"))
    )
    (net (code "6") (name "DEBUG5") (class "Default")
      (node (ref "U1") (pin "H3") (pinfunction "IO_L44N_GCLK20_M3A6_3_H3") (pintype "bidirectional"))
      (node (ref "X3") (pin "6") (pinfunction "6_6") (pintype "bidirectional"))
    )
    (net (code "7") (name "DEBUG6") (class "Default")
      (node (ref "U1") (pin "F1") (pinfunction "IO_L41N_GCLK26_M3DQ5_3_F1") (pintype "bidirectional"))
      (node (ref "X3") (pin "5") (pinfunction "5_5") (pintype "bidirectional"))
    )
    (net (code "8") (name "DEBUG7") (class "Default")
      (node (ref "U1") (pin "E1") (pinfunction "IO_L46N_M3CLKN_3_E1") (pintype "bidirectional"))
      (node (ref "X3") (pin "4") (pinfunction "4_4") (pintype "bidirectional"))
    )
    (net (code "9") (name "DEBUG8") (class "Default")
      (node (ref "U1") (pin "D1") (pinfunction "IO_L49N_M3A2_3_D1") (pintype "bidirectional"))
      (node (ref "X3") (pin "3") (pinfunction "3_3") (pintype "bidirectional"))
    )
    (net (code "10") (name "DEBUG9") (class "Default")
      (node (ref "U1") (pin "C1") (pinfunction "IO_L50P_M3WE_3_C1") (pintype "bidirectional"))
      (node (ref "X3") (pin "2") (pinfunction "2_2") (pintype "bidirectional"))
    )
    (net (code "11") (name "FPGA_DONE") (class "Default")
      (node (ref "R16") (pin "P$1") (pinfunction "1_P$1") (pintype "passive"))
      (node (ref "U1") (pin "P13") (pinfunction "DONE_2_P13") (pintype "bidirectional"))
      (node (ref "U3") (pin "9") (pinfunction "PC1-ADC11_9") (pintype "bidirectional"))
    )
    (net (code "12") (name "FPGA_INIT_B") (class "Default")
      (node (ref "R17") (pin "P$2") (pinfunction "2_P$2") (pintype "passive"))
      (node (ref "U1") (pin "R3") (pinfunction "IO_L65P_INIT_B_2_R3") (pintype "bidirectional"))
      (node (ref "U3") (pin "8") (pinfunction "PC0-ADC10_8") (pintype "bidirectional"))
    )
    (net (code "13") (name "FPGA_PROGRAM_B") (class "Default")
      (node (ref "R15") (pin "P$2") (pinfunction "2_P$2") (pintype "passive"))
      (node (ref "U1") (pin "T2") (pinfunction "PROGRAM_B_2_T2") (pintype "input"))
      (node (ref "U3") (pin "53") (pinfunction "PC12--USART3CK_53") (pintype "bidirectional"))
    )
    (net (code "14") (name "FPGA_TDO_STM_TDI") (class "Default")
      (node (ref "U1") (pin "E14") (pinfunction "TDO_E14") (pintype "output"))
      (node (ref "U3") (pin "50") (pinfunction "PA15/JTDI-TIM2CH1ETR/SPI1NSS_50") (pintype "bidirectional"))
    )
    (net (code "15") (name "FTDI_ADBUS2") (class "Default")
      (node (ref "U1") (pin "T15") (pinfunction "IO_L50N_M1UDQSN_1_T15") (pintype "bidirectional"))
      (node (ref "U7") (pin "15") (pinfunction "AD2_15") (pintype "bidirectional"))
    )
    (net (code "16") (name "FTDI_ADBUS3") (class "Default")
      (node (ref "U1") (pin "R15") (pinfunction "IO_L49P_M1DQ10_1_R15") (pintype "bidirectional"))
      (node (ref "U7") (pin "16") (pinfunction "AD3_16") (pintype "bidirectional"))
    )
    (net (code "17") (name "FTDI_ADBUS4") (class "Default")
      (node (ref "U1") (pin "P16") (pinfunction "IO_L48N_M1DQ9_1_P16") (pintype "bidirectional"))
      (node (ref "U7") (pin "17") (pinfunction "AD4_17") (pintype "bidirectional"))
    )
    (net (code "18") (name "FTDI_ADBUS5") (class "Default")
      (node (ref "U1") (pin "N14") (pinfunction "IO_L45P_A1_M1LDQS_1_N14") (pintype "bidirectional"))
      (node (ref "U7") (pin "18") (pinfunction "AD5_18") (pintype "bidirectional"))
    )
    (net (code "19") (name "FTDI_ADBUS6") (class "Default")
      (node (ref "U1") (pin "N16") (pinfunction "IO_L45N_A0_M1LDQSN_1_N16") (pintype "bidirectional"))
      (node (ref "U7") (pin "19") (pinfunction "AD6_19") (pintype "bidirectional"))
    )
    (net (code "20") (name "FTDI_ADBUS7") (class "Default")
      (node (ref "U1") (pin "M14") (pinfunction "IO_L74N_DOUT_BUSY_1_M14") (pintype "bidirectional"))
      (node (ref "U7") (pin "20") (pinfunction "AD7_20") (pintype "bidirectional"))
    )
    (net (code "21") (name "FTDI_CLKOUT") (class "Default")
      (node (ref "U1") (pin "K14") (pinfunction "IO_L41N_GCLK8_M1CASN_1_K14") (pintype "bidirectional"))
      (node (ref "U7") (pin "29") (pinfunction "AC5_29") (pintype "bidirectional"))
    )
    (net (code "22") (name "FTDI_NOE") (class "Default")
      (node (ref "U1") (pin "K16") (pinfunction "IO_L44N_A2_M1DQ7_1_K16") (pintype "bidirectional"))
      (node (ref "U7") (pin "30") (pinfunction "AC6_30") (pintype "bidirectional"))
    )
    (net (code "23") (name "FTDI_NRD") (class "Default")
      (node (ref "U1") (pin "L14") (pinfunction "IO_L47P_FWE_B_M1DQ0_1_L14") (pintype "bidirectional"))
      (node (ref "U7") (pin "26") (pinfunction "AC2_26") (pintype "bidirectional"))
    )
    (net (code "24") (name "FTDI_NRST") (class "Default")
      (node (ref "U3") (pin "27") (pinfunction "PB1-ADC9/TIM3CH4-TIM1CH3N_27") (pintype "bidirectional"))
      (node (ref "U7") (pin "34") (pinfunction "NRESET_34") (pintype "input"))
    )
    (net (code "25") (name "FTDI_NRXF") (class "Default")
      (node (ref "U1") (pin "M15") (pinfunction "IO_L46P_FCS_B_M1DQ2_1_M15") (pintype "bidirectional"))
      (node (ref "U7") (pin "21") (pinfunction "AC0_21") (pintype "bidirectional"))
    )
    (net (code "26") (name "FTDI_NSIWU") (class "Default")
      (node (ref "U1") (pin "K15") (pinfunction "IO_L44P_A3_M1DQ6_1_K15") (pintype "bidirectional"))
      (node (ref "U7") (pin "28") (pinfunction "AC4_28") (pintype "bidirectional"))
    )
    (net (code "27") (name "FTDI_NTXE") (class "Default")
      (node (ref "U1") (pin "M16") (pinfunction "IO_L46N_FOE_B_M1DQ3_1_M16") (pintype "bidirectional"))
      (node (ref "U7") (pin "25") (pinfunction "AC1_25") (pintype "bidirectional"))
    )
    (net (code "28") (name "FTDI_NWR") (class "Default")
      (node (ref "U1") (pin "L16") (pinfunction "IO_L47N_LDC_M1DQ1_1_L16") (pintype "bidirectional"))
      (node (ref "U7") (pin "27") (pinfunction "AC3_27") (pintype "bidirectional"))
    )
    (net (code "29") (name "GND") (class "Default")
      (node (ref "B1") (pin "P$2") (pinfunction "2_P$2") (pintype "bidirectional"))
      (node (ref "C10") (pin "P$2") (pinfunction "2_P$2") (pintype "passive"))
      (node (ref "C107") (pin "P$2") (pinfunction "2_P$2") (pintype "passive"))
      (node (ref "C11") (pin "P$1") (pinfunction "1_P$1") (pintype "passive"))
      (node (ref "C12") (pin "P$1") (pinfunction "1_P$1") (pintype "passive"))
      (node (ref "C13") (pin "P$1") (pinfunction "1_P$1") (pintype "passive"))
      (node (ref "C15") (pin "P$1") (pinfunction "1_P$1") (pintype "passive"))
      (node (ref "C17") (pin "P$2") (pinfunction "2_P$2") (pintype "passive"))
      (node (ref "C18") (pin "P$2") (pinfunction "2_P$2") (pintype "passive"))
      (node (ref "C19") (pin "P$2") (pinfunction "2_P$2") (pintype "passive"))
      (node (ref "C2") (pin "P$2") (pinfunction "2_P$2") (pintype "passive"))
      (node (ref "C21") (pin "P$2") (pinfunction "2_P$2") (pintype "bidirectional"))
      (node (ref "C22") (pin "P$2") (pinfunction "2_P$2") (pintype "passive"))
      (node (ref "C23") (pin "P$2") (pinfunction "2_P$2") (pintype "passive"))
      (node (ref "C24") (pin "P$2") (pinfunction "2_P$2") (pintype "bidirectional"))
      (node (ref "C25") (pin "P$2") (pinfunction "2_P$2") (pintype "bidirectional"))
      (node (ref "C26") (pin "P$2") (pinfunction "2_P$2") (pintype "bidirectional"))
      (node (ref "C27") (pin "P$2") (pinfunction "2_P$2") (pintype "passive"))
      (node (ref "C28") (pin "P$2") (pinfunction "2_P$2") (pintype "passive"))
      (node (ref "C29") (pin "P$2") (pinfunction "2_P$2") (pintype "passive"))
      (node (ref "C3") (pin "P$2") (pinfunction "2_P$2") (pintype "passive"))
      (node (ref "C30") (pin "P$2") (pinfunction "2_P$2") (pintype "passive"))
      (node (ref "C31") (pin "P$2") (pinfunction "2_P$2") (pintype "passive"))
      (node (ref "C32") (pin "P$2") (pinfunction "2_P$2") (pintype "passive"))
      (node (ref "C33") (pin "P$1") (pinfunction "1_P$1") (pintype "passive"))
      (node (ref "C34") (pin "P$2") (pinfunction "2_P$2") (pintype "passive"))
      (node (ref "C35") (pin "P$2") (pinfunction "2_P$2") (pintype "passive"))
      (node (ref "C36") (pin "P$1") (pinfunction "1_P$1") (pintype "passive"))
      (node (ref "C37") (pin "P$2") (pinfunction "2_P$2") (pintype "passive"))
      (node (ref "C38") (pin "P$2") (pinfunction "2_P$2") (pintype "passive"))
      (node (ref "C39") (pin "P$2") (pinfunction "2_P$2") (pintype "passive"))
      (node (ref "C4") (pin "P$2") (pinfunction "2_P$2") (pintype "passive"))
      (node (ref "C40") (pin "P$2") (pinfunction "2_P$2") (pintype "passive"))
      (node (ref "C41") (pin "P$1") (pinfunction "1_P$1") (pintype "passive"))
      (node (ref "C42") (pin "P$2") (pinfunction "2_P$2") (pintype "passive"))
      (node (ref "C43") (pin "P$2") (pinfunction "2_P$2") (pintype "passive"))
      (node (ref "C44") (pin "P$2") (pinfunction "2_P$2") (pintype "passive"))
      (node (ref "C45") (pin "2") (pinfunction "2_2") (pintype "passive"))
      (node (ref "C46") (pin "P$2") (pinfunction "2_P$2") (pintype "passive"))
      (node (ref "C47") (pin "P$1") (pinfunction "1_P$1") (pintype "passive"))
      (node (ref "C48") (pin "P$2") (pinfunction "2_P$2") (pintype "passive"))
      (node (ref "C49") (pin "P$2") (pinfunction "2_P$2") (pintype "passive"))
      (node (ref "C50") (pin "P$1") (pinfunction "1_P$1") (pintype "passive"))
      (node (ref "C51") (pin "P$1") (pinfunction "1_P$1") (pintype "passive"))
      (node (ref "C52") (pin "P$2") (pinfunction "2_P$2") (pintype "passive"))
      (node (ref "C53") (pin "P$2") (pinfunction "2_P$2") (pintype "passive"))
      (node (ref "C54") (pin "P$2") (pinfunction "2_P$2") (pintype "passive"))
      (node (ref "C55") (pin "P$2") (pinfunction "2_P$2") (pintype "passive"))
      (node (ref "C56") (pin "P$2") (pinfunction "2_P$2") (pintype "passive"))
      (node (ref "C57") (pin "P$1") (pinfunction "1_P$1") (pintype "passive"))
      (node (ref "C58") (pin "P$2") (pinfunction "2_P$2") (pintype "passive"))
      (node (ref "C59") (pin "P$1") (pinfunction "1_P$1") (pintype "passive"))
      (node (ref "C6") (pin "P$1") (pinfunction "1_P$1") (pintype "passive"))
      (node (ref "C60") (pin "P$2") (pinfunction "2_P$2") (pintype "passive"))
      (node (ref "C61") (pin "P$2") (pinfunction "2_P$2") (pintype "passive"))
      (node (ref "C62") (pin "P$2") (pinfunction "2_P$2") (pintype "passive"))
      (node (ref "C63") (pin "P$2") (pinfunction "2_P$2") (pintype "passive"))
      (node (ref "C64") (pin "P$2") (pinfunction "2_P$2") (pintype "passive"))
      (node (ref "C65") (pin "P$1") (pinfunction "1_P$1") (pintype "passive"))
      (node (ref "C66") (pin "P$2") (pinfunction "2_P$2") (pintype "passive"))
      (node (ref "C67") (pin "P$2") (pinfunction "2_P$2") (pintype "passive"))
      (node (ref "C68") (pin "P$2") (pinfunction "2_P$2") (pintype "passive"))
      (node (ref "C69") (pin "2") (pinfunction "2_2") (pintype "passive"))
      (node (ref "C7") (pin "P$1") (pinfunction "1_P$1") (pintype "passive"))
      (node (ref "C70") (pin "P$2") (pinfunction "2_P$2") (pintype "passive"))
      (node (ref "C71") (pin "P$2") (pinfunction "2_P$2") (pintype "passive"))
      (node (ref "C72") (pin "P$2") (pinfunction "2_P$2") (pintype "passive"))
      (node (ref "C73") (pin "P$2") (pinfunction "2_P$2") (pintype "passive"))
      (node (ref "C74") (pin "P$2") (pinfunction "2_P$2") (pintype "passive"))
      (node (ref "C75") (pin "P$2") (pinfunction "2_P$2") (pintype "passive"))
      (node (ref "C76") (pin "P$2") (pinfunction "2_P$2") (pintype "passive"))
      (node (ref "C77") (pin "P$2") (pinfunction "2_P$2") (pintype "passive"))
      (node (ref "C78") (pin "P$2") (pinfunction "2_P$2") (pintype "passive"))
      (node (ref "C8") (pin "P$2") (pinfunction "2_P$2") (pintype "passive"))
      (node (ref "C80") (pin "P$2") (pinfunction "2_P$2") (pintype "passive"))
      (node (ref "C81") (pin "P$2") (pinfunction "2_P$2") (pintype "passive"))
      (node (ref "C82") (pin "P$1") (pinfunction "1_P$1") (pintype "passive"))
      (node (ref "C86") (pin "P$2") (pinfunction "2_P$2") (pintype "bidirectional"))
      (node (ref "C87") (pin "P$2") (pinfunction "2_P$2") (pintype "bidirectional"))
      (node (ref "C9") (pin "P$2") (pinfunction "2_P$2") (pintype "passive"))
      (node (ref "C96") (pin "P$2") (pinfunction "2_P$2") (pintype "passive"))
      (node (ref "H2") (pin "B3,0") (pinfunction "MOUNT_B3,0") (pintype "passive"))
      (node (ref "H3") (pin "B3,0") (pinfunction "MOUNT_B3,0") (pintype "passive"))
      (node (ref "H4") (pin "B3,0") (pinfunction "MOUNT_B3,0") (pintype "passive"))
      (node (ref "H5") (pin "B3,0") (pinfunction "MOUNT_B3,0") (pintype "passive"))
      (node (ref "J1") (pin "P2") (pinfunction "2_P2") (pintype "power_in"))
      (node (ref "J1") (pin "P3") (pinfunction "3_P3") (pintype "power_in"))
      (node (ref "J1") (pin "P4") (pinfunction "4_P4") (pintype "power_in"))
      (node (ref "J1") (pin "P5") (pinfunction "5_P5") (pintype "power_in"))
      (node (ref "J6") (pin "PIN_5") (pinfunction "5_PIN_5") (pintype "input"))
      (node (ref "L5") (pin "P$1") (pinfunction "1_P$1") (pintype "passive"))
      (node (ref "Q1") (pin "1") (pinfunction "G_1") (pintype "passive"))
      (node (ref "R14") (pin "P$2") (pinfunction "2_P$2") (pintype "passive"))
      (node (ref "R18") (pin "P$1") (pinfunction "1_P$1") (pintype "passive"))
      (node (ref "R20") (pin "P$1") (pinfunction "1_P$1") (pintype "passive"))
      (node (ref "R62") (pin "P$2") (pinfunction "2_P$2") (pintype "passive"))
      (node (ref "R63") (pin "P$2") (pinfunction "2_P$2") (pintype "passive"))
      (node (ref "R7") (pin "P$2") (pinfunction "2_P$2") (pintype "passive"))
      (node (ref "R8") (pin "P$1") (pinfunction "1_P$1") (pintype "passive"))
      (node (ref "SHLD2") (pin "1") (pinfunction "P$1_1") (pintype "power_in"))
      (node (ref "SHLD2") (pin "10") (pinfunction "P$10_10") (pintype "power_in"))
      (node (ref "SHLD2") (pin "11") (pinfunction "P$11_11") (pintype "power_in"))
      (node (ref "SHLD2") (pin "12") (pinfunction "P$12_12") (pintype "power_in"))
      (node (ref "SHLD2") (pin "13") (pinfunction "P$13_13") (pintype "power_in"))
      (node (ref "SHLD2") (pin "14") (pinfunction "P$14_14") (pintype "power_in"))
      (node (ref "SHLD2") (pin "15") (pinfunction "P$15_15") (pintype "power_in"))
      (node (ref "SHLD2") (pin "16") (pinfunction "P$16_16") (pintype "power_in"))
      (node (ref "SHLD2") (pin "17") (pinfunction "P$17_17") (pintype "power_in"))
      (node (ref "SHLD2") (pin "18") (pinfunction "P$18_18") (pintype "power_in"))
      (node (ref "SHLD2") (pin "19") (pinfunction "P$19_19") (pintype "power_in"))
      (node (ref "SHLD2") (pin "2") (pinfunction "P$2_2") (pintype "power_in"))
      (node (ref "SHLD2") (pin "20") (pinfunction "P$20_20") (pintype "power_in"))
      (node (ref "SHLD2") (pin "21") (pinfunction "P$21_21") (pintype "power_in"))
      (node (ref "SHLD2") (pin "22") (pinfunction "P$22_22") (pintype "power_in"))
      (node (ref "SHLD2") (pin "23") (pinfunction "P$23_23") (pintype "power_in"))
      (node (ref "SHLD2") (pin "24") (pinfunction "P$24_24") (pintype "power_in"))
      (node (ref "SHLD2") (pin "25") (pinfunction "P$25_25") (pintype "power_in"))
      (node (ref "SHLD2") (pin "26") (pinfunction "P$26_26") (pintype "power_in"))
      (node (ref "SHLD2") (pin "27") (pinfunction "P$27_27") (pintype "power_in"))
      (node (ref "SHLD2") (pin "28") (pinfunction "P$28_28") (pintype "power_in"))
      (node (ref "SHLD2") (pin "3") (pinfunction "P$3_3") (pintype "power_in"))
      (node (ref "SHLD2") (pin "4") (pinfunction "P$4_4") (pintype "power_in"))
      (node (ref "SHLD2") (pin "5") (pinfunction "P$5_5") (pintype "power_in"))
      (node (ref "SHLD2") (pin "6") (pinfunction "P$6_6") (pintype "power_in"))
      (node (ref "SHLD2") (pin "7") (pinfunction "P$7_7") (pintype "power_in"))
      (node (ref "SHLD2") (pin "8") (pinfunction "P$8_8") (pintype "power_in"))
      (node (ref "SHLD2") (pin "9") (pinfunction "P$9_9") (pintype "power_in"))
      (node (ref "U1") (pin "A1") (pinfunction "GND_A1") (pintype "power_in"))
      (node (ref "U1") (pin "A16") (pinfunction "GND_A16") (pintype "power_in"))
      (node (ref "U1") (pin "B11") (pinfunction "GND_B11") (pintype "power_in"))
      (node (ref "U1") (pin "B7") (pinfunction "GND_B7") (pintype "power_in"))
      (node (ref "U1") (pin "D13") (pinfunction "GND_D13") (pintype "power_in"))
      (node (ref "U1") (pin "D4") (pinfunction "GND_D4") (pintype "power_in"))
      (node (ref "U1") (pin "E9") (pinfunction "GND_E9") (pintype "power_in"))
      (node (ref "U1") (pin "G15") (pinfunction "GND_G15") (pintype "power_in"))
      (node (ref "U1") (pin "G2") (pinfunction "GND_G2") (pintype "power_in"))
      (node (ref "U1") (pin "G8") (pinfunction "GND_G8") (pintype "power_in"))
      (node (ref "U1") (pin "H12") (pinfunction "GND_H12") (pintype "power_in"))
      (node (ref "U1") (pin "H7") (pinfunction "GND_H7") (pintype "power_in"))
      (node (ref "U1") (pin "H9") (pinfunction "GND_H9") (pintype "power_in"))
      (node (ref "U1") (pin "J5") (pinfunction "GND_J5") (pintype "power_in"))
      (node (ref "U1") (pin "J8") (pinfunction "GND_J8") (pintype "power_in"))
      (node (ref "U1") (pin "K7") (pinfunction "GND_K7") (pintype "power_in"))
      (node (ref "U1") (pin "K9") (pinfunction "GND_K9") (pintype "power_in"))
      (node (ref "U1") (pin "L15") (pinfunction "GND_L15") (pintype "power_in"))
      (node (ref "U1") (pin "L2") (pinfunction "GND_L2") (pintype "power_in"))
      (node (ref "U1") (pin "M8") (pinfunction "GND_M8") (pintype "power_in"))
      (node (ref "U1") (pin "N11") (pinfunction "IO_L13P_M1_2_N11") (pintype "bidirectional"))
      (node (ref "U1") (pin "N13") (pinfunction "GND_N13") (pintype "power_in"))
      (node (ref "U1") (pin "P3") (pinfunction "GND_P3") (pintype "power_in"))
      (node (ref "U1") (pin "R10") (pinfunction "GND_R10") (pintype "power_in"))
      (node (ref "U1") (pin "R6") (pinfunction "GND_R6") (pintype "power_in"))
      (node (ref "U1") (pin "T1") (pinfunction "GND_T1") (pintype "power_in"))
      (node (ref "U1") (pin "T16") (pinfunction "GND_T16") (pintype "power_in"))
      (node (ref "U10") (pin "29") (pinfunction "EPGND_29") (pintype "bidirectional"))
      (node (ref "U12") (pin "2") (pinfunction "GND_2") (pintype "bidirectional"))
      (node (ref "U13") (pin "4") (pinfunction "GND_4") (pintype "power_in"))
      (node (ref "U13") (pin "9") (pinfunction "EP_9") (pintype "power_in"))
      (node (ref "U2") (pin "11") (pinfunction "GND2_11") (pintype "bidirectional"))
      (node (ref "U2") (pin "5") (pinfunction "GND1_5") (pintype "bidirectional"))
      (node (ref "U3") (pin "12") (pinfunction "VSSA_12") (pintype "power_in"))
      (node (ref "U3") (pin "18") (pinfunction "VSS4_18") (pintype "bidirectional"))
      (node (ref "U3") (pin "60") (pinfunction "BOOT0_60") (pintype "input"))
      (node (ref "U3") (pin "63") (pinfunction "VSS3_63") (pintype "power_in"))
      (node (ref "U4") (pin "1") (pinfunction "GND1_1") (pintype "bidirectional"))
      (node (ref "U4") (pin "2") (pinfunction "GND2_2") (pintype "bidirectional"))
      (node (ref "U5") (pin "2") (pinfunction "2_2") (pintype "power_in"))
      (node (ref "U5") (pin "3") (pinfunction "3_3") (pintype "power_in"))
      (node (ref "U5") (pin "4") (pinfunction "4_4") (pintype "power_in"))
      (node (ref "U5") (pin "5") (pinfunction "5_5") (pintype "power_in"))
      (node (ref "U6") (pin "2") (pinfunction "VSS_2") (pintype "power_in"))
      (node (ref "U7") (pin "10") (pinfunction "GND1_10") (pintype "power_in"))
      (node (ref "U7") (pin "11") (pinfunction "GND2_11") (pintype "power_in"))
      (node (ref "U7") (pin "22") (pinfunction "GND3_22") (pintype "power_in"))
      (node (ref "U7") (pin "23") (pinfunction "GND4_23") (pintype "power_in"))
      (node (ref "U7") (pin "35") (pinfunction "GND5_35") (pintype "power_in"))
      (node (ref "U7") (pin "36") (pinfunction "GND6_36") (pintype "power_in"))
      (node (ref "U7") (pin "4") (pinfunction "AGND1_4") (pintype "power_in"))
      (node (ref "U7") (pin "41") (pinfunction "AGND3_41") (pintype "power_in"))
      (node (ref "U7") (pin "42") (pinfunction "TEST_42") (pintype "input"))
      (node (ref "U7") (pin "47") (pinfunction "GND7_47") (pintype "power_in"))
      (node (ref "U7") (pin "48") (pinfunction "GND8_48") (pintype "power_in"))
      (node (ref "U7") (pin "49") (pinfunction "EPGND_49") (pintype "power_in"))
      (node (ref "U7") (pin "9") (pinfunction "AGND2_9") (pintype "power_in"))
      (node (ref "U8") (pin "2") (pinfunction "GND1_2") (pintype "power_in"))
      (node (ref "U8") (pin "3") (pinfunction "GND2_3") (pintype "power_in"))
      (node (ref "U8") (pin "5") (pinfunction "GND3_5") (pintype "power_in"))
      (node (ref "U9") (pin "3") (pinfunction "VSS_3") (pintype "bidirectional"))
      (node (ref "X1") (pin "1") (pinfunction "1_1") (pintype "bidirectional"))
      (node (ref "X3") (pin "1") (pinfunction "1_1") (pintype "bidirectional"))
      (node (ref "X5") (pin "3") (pinfunction "3_3") (pintype "bidirectional"))
      (node (ref "X5") (pin "5") (pinfunction "5_5") (pintype "bidirectional"))
      (node (ref "X5") (pin "7") (pinfunction "7_7") (pintype "bidirectional"))
      (node (ref "X5") (pin "9") (pinfunction "9_9") (pintype "bidirectional"))
      (node (ref "X6") (pin "1") (pinfunction "1_1") (pintype "bidirectional"))
    )
    (net (code "30") (name "JTAG_RST") (class "Default")
      (node (ref "B1") (pin "P$1") (pinfunction "1_P$1") (pintype "bidirectional"))
      (node (ref "C32") (pin "P$1") (pinfunction "1_P$1") (pintype "passive"))
      (node (ref "R34") (pin "P$1") (pinfunction "1_P$1") (pintype "passive"))
      (node (ref "U3") (pin "7") (pinfunction "NRST_7") (pintype "bidirectional"))
      (node (ref "X5") (pin "10") (pinfunction "10_10") (pintype "bidirectional"))
    )
    (net (code "31") (name "JTAG_TCK") (class "Default")
      (node (ref "U1") (pin "C14") (pinfunction "TCK_C14") (pintype "input"))
      (node (ref "U3") (pin "49") (pinfunction "PA14/JTCK/SWCLK_49") (pintype "bidirectional"))
      (node (ref "X5") (pin "4") (pinfunction "4_4") (pintype "bidirectional"))
    )
    (net (code "32") (name "JTAG_TDI") (class "Default")
      (node (ref "U1") (pin "C12") (pinfunction "TDI_C12") (pintype "input"))
      (node (ref "X5") (pin "8") (pinfunction "8_8") (pintype "bidirectional"))
    )
    (net (code "33") (name "JTAG_TDO") (class "Default")
      (node (ref "U3") (pin "55") (pinfunction "PB3/JTDO--TIM2CH2/TRACESWO/SPI1SCK_55") (pintype "bidirectional"))
      (node (ref "X5") (pin "6") (pinfunction "6_6") (pintype "bidirectional"))
    )
    (net (code "34") (name "JTAG_TMS") (class "Default")
      (node (ref "U1") (pin "A15") (pinfunction "TMS_A15") (pintype "input"))
      (node (ref "U3") (pin "46") (pinfunction "PA13/JTMS/SWDIO_46") (pintype "bidirectional"))
      (node (ref "X5") (pin "2") (pinfunction "2_2") (pintype "bidirectional"))
    )
    (net (code "35") (name "MAX_ANT_FLAG") (class "Default")
      (node (ref "U10") (pin "1") (pinfunction "ANT_FLAG_1") (pintype "bidirectional"))
      (node (ref "U3") (pin "25") (pinfunction "PC5-ADC15_25") (pintype "bidirectional"))
    )
    (net (code "36") (name "MAX_CLKOUT") (class "Default")
      (node (ref "U1") (pin "J14") (pinfunction "IO_L43P_GCLK5_M1DQ4_1_J14") (pintype "bidirectional"))
      (node (ref "U10") (pin "16") (pinfunction "CLK_OUT_16") (pintype "bidirectional"))
    )
    (net (code "37") (name "MAX_I0") (class "Default")
      (node (ref "U1") (pin "E16") (pinfunction "IO_L34N_A12_M1BA2_1_E16") (pintype "bidirectional"))
      (node (ref "U10") (pin "20") (pinfunction "I0_20") (pintype "bidirectional"))
    )
    (net (code "38") (name "MAX_I1") (class "Default")
      (node (ref "U1") (pin "E15") (pinfunction "IO_L34P_A13_M1WE_1_E15") (pintype "bidirectional"))
      (node (ref "U10") (pin "21") (pinfunction "I1_21") (pintype "bidirectional"))
    )
    (net (code "39") (name "MAX_LD") (class "Default")
      (node (ref "U10") (pin "6") (pinfunction "LD_6") (pintype "bidirectional"))
      (node (ref "U3") (pin "41") (pinfunction "PA8-USART1CK/MCO/TIM1CH1_41") (pintype "bidirectional"))
    )
    (net (code "40") (name "MAX_NIDLE") (class "Default")
      (node (ref "R12") (pin "P$1") (pinfunction "1_P$1") (pintype "passive"))
      (node (ref "U10") (pin "24") (pinfunction "~{IDLE}_24") (pintype "bidirectional"))
      (node (ref "U3") (pin "29") (pinfunction "PB10-I2C2SCL/USART3TX-TIM2CH3_29") (pintype "bidirectional"))
    )
    (net (code "41") (name "MAX_NSHDN") (class "Default")
      (node (ref "R19") (pin "P$1") (pinfunction "1_P$1") (pintype "passive"))
      (node (ref "U10") (pin "7") (pinfunction "~{SHDN}_7") (pintype "bidirectional"))
      (node (ref "U3") (pin "62") (pinfunction "PB9-TIM4CH4-I2C1SDA/CANTX_62") (pintype "bidirectional"))
    )
    (net (code "42") (name "MAX_PGM") (class "Default")
      (node (ref "R20") (pin "P$2") (pinfunction "2_P$2") (pintype "passive"))
      (node (ref "U10") (pin "26") (pinfunction "PGM_26") (pintype "bidirectional"))
      (node (ref "U3") (pin "61") (pinfunction "PB8-TIM4CH3-I2C1SCL/CANRX_61") (pintype "bidirectional"))
    )
    (net (code "43") (name "MAX_Q0") (class "Default")
      (node (ref "U1") (pin "F15") (pinfunction "IO_L35P_A11_M1A7_1_F15") (pintype "bidirectional"))
      (node (ref "U10") (pin "18") (pinfunction "Q0_18") (pintype "bidirectional"))
    )
    (net (code "44") (name "MAX_Q1") (class "Default")
      (node (ref "U1") (pin "F16") (pinfunction "IO_L35N_A10_M1A2_1_F16") (pintype "bidirectional"))
      (node (ref "U10") (pin "17") (pinfunction "Q1_17") (pintype "bidirectional"))
    )
    (net (code "45") (name "Net-(C1-1)") (class "Default")
      (node (ref "C1") (pin "P$1") (pinfunction "1_P$1") (pintype "passive"))
      (node (ref "R61") (pin "P$1") (pinfunction "1_P$1") (pintype "passive"))
      (node (ref "R62") (pin "P$1") (pinfunction "1_P$1") (pintype "passive"))
      (node (ref "U2") (pin "1") (pinfunction "VFB1_1") (pintype "bidirectional"))
    )
    (net (code "46") (name "Net-(C5-2)") (class "Default")
      (node (ref "C5") (pin "P$2") (pinfunction "2_P$2") (pintype "passive"))
      (node (ref "R63") (pin "P$1") (pinfunction "1_P$1") (pintype "passive"))
      (node (ref "R64") (pin "P$1") (pinfunction "1_P$1") (pintype "passive"))
      (node (ref "U2") (pin "10") (pinfunction "VFB2_10") (pintype "bidirectional"))
    )
    (net (code "47") (name "Net-(C7-2)") (class "Default")
      (node (ref "C7") (pin "P$2") (pinfunction "2_P$2") (pintype "passive"))
      (node (ref "C9") (pin "P$1") (pinfunction "1_P$1") (pintype "passive"))
      (node (ref "R65") (pin "P$2") (pinfunction "2_P$2") (pintype "passive"))
      (node (ref "U12") (pin "1") (pinfunction "VIN_1") (pintype "bidirectional"))
      (node (ref "U12") (pin "3") (pinfunction "EN_3") (pintype "bidirectional"))
    )
    (net (code "48") (name "Net-(C12-2)") (class "Default")
      (node (ref "C12") (pin "P$2") (pinfunction "2_P$2") (pintype "passive"))
      (node (ref "C13") (pin "P$2") (pinfunction "2_P$2") (pintype "passive"))
      (node (ref "C36") (pin "P$2") (pinfunction "2_P$2") (pintype "passive"))
      (node (ref "C41") (pin "P$2") (pinfunction "2_P$2") (pintype "passive"))
      (node (ref "L1") (pin "P$1") (pinfunction "1_P$1") (pintype "passive"))
      (node (ref "L3") (pin "P$2") (pinfunction "2_P$2") (pintype "passive"))
      (node (ref "U10") (pin "3") (pinfunction "ANT_BIAS_3") (pintype "bidirectional"))
    )
    (net (code "49") (name "Net-(C14-1)") (class "Default")
      (node (ref "C14") (pin "P$1") (pinfunction "1_P$1") (pintype "passive"))
      (node (ref "J1") (pin "P1") (pinfunction "1_P1") (pintype "bidirectional"))
      (node (ref "L3") (pin "P$1") (pinfunction "1_P$1") (pintype "passive"))
    )
    (net (code "50") (name "Net-(C14-2)") (class "Default")
      (node (ref "C14") (pin "P$2") (pinfunction "2_P$2") (pintype "passive"))
      (node (ref "U10") (pin "25") (pinfunction "LNA_IN2_25") (pintype "bidirectional"))
    )
    (net (code "51") (name "Net-(C15-2)") (class "Default")
      (node (ref "C15") (pin "P$2") (pinfunction "2_P$2") (pintype "passive"))
      (node (ref "C47") (pin "P$2") (pinfunction "2_P$2") (pintype "passive"))
      (node (ref "R11") (pin "P$1") (pinfunction "1_P$1") (pintype "passive"))
      (node (ref "U9") (pin "1") (pinfunction "VDD_1") (pintype "bidirectional"))
    )
    (net (code "52") (name "Net-(C16-1)") (class "Default")
      (node (ref "C16") (pin "P$1") (pinfunction "1_P$1") (pintype "passive"))
      (node (ref "L1") (pin "P$2") (pinfunction "2_P$2") (pintype "passive"))
      (node (ref "U5") (pin "1") (pinfunction "1_1") (pintype "bidirectional"))
    )
    (net (code "53") (name "Net-(C16-2)") (class "Default")
      (node (ref "C16") (pin "P$2") (pinfunction "2_P$2") (pintype "passive"))
      (node (ref "L4") (pin "P$1") (pinfunction "1_P$1") (pintype "passive"))
      (node (ref "L5") (pin "P$2") (pinfunction "2_P$2") (pintype "passive"))
    )
    (net (code "54") (name "Net-(C18-1)") (class "Default")
      (node (ref "C18") (pin "P$1") (pinfunction "1_P$1") (pintype "passive"))
      (node (ref "R2") (pin "P$1") (pinfunction "1_P$1") (pintype "passive"))
    )
    (net (code "55") (name "Net-(C19-1)") (class "Default")
      (node (ref "C19") (pin "P$1") (pinfunction "1_P$1") (pintype "passive"))
      (node (ref "R2") (pin "P$2") (pinfunction "2_P$2") (pintype "passive"))
      (node (ref "U10") (pin "12") (pinfunction "CP_OUT_12") (pintype "bidirectional"))
    )
    (net (code "56") (name "Net-(C20-1)") (class "Default")
      (node (ref "C20") (pin "P$1") (pinfunction "1_P$1") (pintype "passive"))
      (node (ref "U10") (pin "15") (pinfunction "XTAL_15") (pintype "bidirectional"))
    )
    (net (code "57") (name "Net-(C20-2)") (class "Default")
      (node (ref "C20") (pin "P$2") (pinfunction "2_P$2") (pintype "passive"))
      (node (ref "U4") (pin "3") (pinfunction "OUT_3") (pintype "bidirectional"))
    )
    (net (code "58") (name "Net-(C34-1)") (class "Default")
      (node (ref "C34") (pin "P$1") (pinfunction "1_P$1") (pintype "passive"))
      (node (ref "U7") (pin "2") (pinfunction "XCSO_2") (pintype "output"))
      (node (ref "X4") (pin "2") (pinfunction "2_2") (pintype "bidirectional"))
    )
    (net (code "59") (name "Net-(C35-1)") (class "Default")
      (node (ref "C35") (pin "P$1") (pinfunction "1_P$1") (pintype "passive"))
      (node (ref "U7") (pin "1") (pinfunction "XCSI_1") (pintype "input"))
      (node (ref "X4") (pin "1") (pinfunction "1_1") (pintype "bidirectional"))
    )
    (net (code "60") (name "Net-(C38-1)") (class "Default")
      (node (ref "C38") (pin "P$1") (pinfunction "1_P$1") (pintype "passive"))
      (node (ref "L2") (pin "P$1") (pinfunction "1_P$1") (pintype "passive"))
      (node (ref "U10") (pin "4") (pinfunction "VCCRF_4") (pintype "bidirectional"))
    )
    (net (code "61") (name "Net-(C49-1)") (class "Default")
      (node (ref "C49") (pin "P$1") (pinfunction "1_P$1") (pintype "passive"))
      (node (ref "U7") (pin "38") (pinfunction "VCCCORE_38") (pintype "output"))
    )
    (net (code "62") (name "Net-(C59-2)") (class "Default")
      (node (ref "C59") (pin "P$2") (pinfunction "2_P$2") (pintype "passive"))
      (node (ref "C64") (pin "P$1") (pinfunction "1_P$1") (pintype "passive"))
      (node (ref "L10") (pin "P$2") (pinfunction "2_P$2") (pintype "passive"))
      (node (ref "U7") (pin "3") (pinfunction "VPHY_3") (pintype "power_in"))
    )
    (net (code "63") (name "Net-(C65-2)") (class "Default")
      (node (ref "C65") (pin "P$2") (pinfunction "2_P$2") (pintype "passive"))
      (node (ref "C68") (pin "P$1") (pinfunction "1_P$1") (pintype "passive"))
      (node (ref "L11") (pin "P$2") (pinfunction "2_P$2") (pintype "passive"))
      (node (ref "U7") (pin "8") (pinfunction "VPLL_8") (pintype "power_in"))
    )
    (net (code "64") (name "Net-(C66-1)") (class "Default")
      (node (ref "C66") (pin "P$1") (pinfunction "1_P$1") (pintype "passive"))
      (node (ref "U3") (pin "31") (pinfunction "VSS1_31") (pintype "power_in"))
    )
    (net (code "65") (name "Net-(C75-1)") (class "Default")
      (node (ref "C75") (pin "P$1") (pinfunction "1_P$1") (pintype "passive"))
      (node (ref "U7") (pin "37") (pinfunction "VCCA_37") (pintype "output"))
    )
    (net (code "66") (name "Net-(C82-2)") (class "Default")
      (node (ref "C82") (pin "P$2") (pinfunction "2_P$2") (pintype "passive"))
      (node (ref "U3") (pin "47") (pinfunction "VSS2_47") (pintype "power_in"))
    )
    (net (code "67") (name "Net-(C95-1)") (class "Default")
      (node (ref "C95") (pin "P$1") (pinfunction "1_P$1") (pintype "passive"))
      (node (ref "U9") (pin "2") (pinfunction "RFOUT_2") (pintype "bidirectional"))
    )
    (net (code "68") (name "Net-(C95-2)") (class "Default")
      (node (ref "C95") (pin "P$2") (pinfunction "2_P$2") (pintype "passive"))
      (node (ref "U10") (pin "27") (pinfunction "LNA_IN1_27") (pintype "bidirectional"))
    )
    (net (code "69") (name "Net-(L4-2)") (class "Default")
      (node (ref "L4") (pin "P$2") (pinfunction "2_P$2") (pintype "passive"))
      (node (ref "U9") (pin "4") (pinfunction "RFIN_4") (pintype "bidirectional"))
    )
    (net (code "70") (name "Net-(R1-1)") (class "Default")
      (node (ref "R1") (pin "P$1") (pinfunction "1_P$1") (pintype "passive"))
      (node (ref "U2") (pin "8") (pinfunction "NPOR_8") (pintype "bidirectional"))
    )
    (net (code "71") (name "Net-(R3-1)") (class "Default")
      (node (ref "R3") (pin "P$1") (pinfunction "1_P$1") (pintype "passive"))
      (node (ref "R6") (pin "P$2") (pinfunction "2_P$2") (pintype "passive"))
      (node (ref "U6") (pin "3") (pinfunction "DI_3") (pintype "input"))
      (node (ref "U7") (pin "43") (pinfunction "EEDATA_43") (pintype "bidirectional"))
    )
    (net (code "72") (name "Net-(R3-2)") (class "Default")
      (node (ref "R3") (pin "P$2") (pinfunction "2_P$2") (pintype "passive"))
      (node (ref "U6") (pin "1") (pinfunction "DO_1") (pintype "output"))
    )
    (net (code "73") (name "Net-(R4-2)") (class "Default")
      (node (ref "R4") (pin "P$2") (pinfunction "2_P$2") (pintype "passive"))
      (node (ref "U6") (pin "5") (pinfunction "CS_5") (pintype "input"))
      (node (ref "U7") (pin "45") (pinfunction "EECS_45") (pintype "bidirectional"))
    )
    (net (code "74") (name "Net-(R5-2)") (class "Default")
      (node (ref "R5") (pin "P$2") (pinfunction "2_P$2") (pintype "passive"))
      (node (ref "U6") (pin "4") (pinfunction "CLK_4") (pintype "input"))
      (node (ref "U7") (pin "44") (pinfunction "EECLK_44") (pintype "output"))
    )
    (net (code "75") (name "Net-(R7-1)") (class "Default")
      (node (ref "R7") (pin "P$1") (pinfunction "1_P$1") (pintype "passive"))
      (node (ref "U7") (pin "5") (pinfunction "REF_5") (pintype "input"))
    )
    (net (code "76") (name "Net-(R9-2)") (class "Default")
      (node (ref "R9") (pin "P$2") (pinfunction "2_P$2") (pintype "passive"))
      (node (ref "U7") (pin "31") (pinfunction "AC7_31") (pintype "bidirectional"))
    )
    (net (code "77") (name "Net-(R10-1)") (class "Default")
      (node (ref "R10") (pin "P$1") (pinfunction "1_P$1") (pintype "passive"))
      (node (ref "U3") (pin "26") (pinfunction "PB0-ADC8/TIM3CH3-TIM1CH2N_26") (pintype "bidirectional"))
    )
    (net (code "78") (name "Net-(R14-1)") (class "Default")
      (node (ref "R14") (pin "P$1") (pinfunction "1_P$1") (pintype "passive"))
      (node (ref "U1") (pin "P14") (pinfunction "SUSPEND_P14") (pintype "input"))
    )
    (net (code "79") (name "Net-(R18-2)") (class "Default")
      (node (ref "R18") (pin "P$2") (pinfunction "2_P$2") (pintype "passive"))
      (node (ref "U1") (pin "C4") (pinfunction "IO_L1P_HSWAPEN_0_C4") (pintype "bidirectional"))
    )
    (net (code "80") (name "Net-(R28-2)") (class "Default")
      (node (ref "LED2") (pin "A") (pinfunction "A_A") (pintype "passive"))
      (node (ref "R28") (pin "P$2") (pinfunction "2_P$2") (pintype "passive"))
    )
    (net (code "81") (name "Net-(R30-1)") (class "Default")
      (node (ref "LED1") (pin "A") (pinfunction "A_A") (pintype "passive"))
      (node (ref "R30") (pin "P$1") (pinfunction "1_P$1") (pintype "passive"))
    )
    (net (code "82") (name "Net-(U2-SW1)") (class "Default")
      (node (ref "L13") (pin "2") (pinfunction "2_2") (pintype "bidirectional"))
      (node (ref "U2") (pin "4") (pinfunction "SW1_4") (pintype "bidirectional"))
    )
    (net (code "83") (name "Net-(U2-SW2)") (class "Default")
      (node (ref "L14") (pin "1") (pinfunction "1_1") (pintype "bidirectional"))
      (node (ref "U2") (pin "7") (pinfunction "SW2_7") (pintype "bidirectional"))
    )
    (net (code "84") (name "Net-(U3-PC3-ADC13)") (class "Default")
      (node (ref "LED2") (pin "C") (pinfunction "C_C") (pintype "passive"))
      (node (ref "U3") (pin "11") (pinfunction "PC3-ADC13_11") (pintype "bidirectional"))
    )
    (net (code "85") (name "Net-(U3-PC4-ADC14)") (class "Default")
      (node (ref "LED1") (pin "C") (pinfunction "C_C") (pintype "passive"))
      (node (ref "U3") (pin "24") (pinfunction "PC4-ADC14_24") (pintype "bidirectional"))
    )
    (net (code "86") (name "Net-(U10A-LNA_OUT)") (class "Default")
      (node (ref "U10") (pin "2") (pinfunction "LNA_OUT_2") (pintype "bidirectional"))
      (node (ref "U8") (pin "1") (pinfunction "RFIN_1") (pintype "bidirectional"))
    )
    (net (code "87") (name "Net-(U10A-MIX_IN)") (class "Default")
      (node (ref "U10") (pin "5") (pinfunction "MIX_IN_5") (pintype "bidirectional"))
      (node (ref "U8") (pin "4") (pinfunction "RFOUT_4") (pintype "bidirectional"))
    )
    (net (code "88") (name "SPI1MISO") (class "Default")
      (node (ref "U1") (pin "A12") (pinfunction "IO_L62N_VREF_0_A12") (pintype "bidirectional"))
      (node (ref "U3") (pin "22") (pinfunction "PA6-SPI1MISO/ADC6/TIM3CH1-TIM1BKIN_22") (pintype "bidirectional"))
    )
    (net (code "89") (name "SPI1MOSI") (class "Default")
      (node (ref "U1") (pin "C11") (pinfunction "IO_L39P_0_C11") (pintype "bidirectional"))
      (node (ref "U3") (pin "23") (pinfunction "PA7-SPI1MOSI/ADC7/TIM3CH2-TIM1CH1N_23") (pintype "bidirectional"))
    )
    (net (code "90") (name "SPI1NSS") (class "Default")
      (node (ref "U1") (pin "A10") (pinfunction "IO_L35N_GCLK16_0_A10") (pintype "bidirectional"))
      (node (ref "U3") (pin "20") (pinfunction "PA4-SPI1NSS/ADC4/USART2CK_20") (pintype "bidirectional"))
    )
    (net (code "91") (name "SPI1SCK") (class "Default")
      (node (ref "U1") (pin "B10") (pinfunction "IO_L35P_GCLK17_0_B10") (pintype "bidirectional"))
      (node (ref "U3") (pin "21") (pinfunction "PA5-SPI1SCK/ADC5_21") (pintype "bidirectional"))
    )
    (net (code "92") (name "SPI2MISO") (class "Default")
      (node (ref "U1") (pin "P10") (pinfunction "IO_L3P_D0_DIN_MISO_MISO1_2_P10") (pintype "bidirectional"))
      (node (ref "U13") (pin "2") (pinfunction "DO_2") (pintype "bidirectional"))
      (node (ref "U3") (pin "35") (pinfunction "PB14-SPI2MISO/USART3RTS/TIM1CH2N_35") (pintype "bidirectional"))
    )
    (net (code "93") (name "SPI2MOSI") (class "Default")
      (node (ref "U1") (pin "T10") (pinfunction "IO_L3N_MOSI_CSI_B_MISO0_2_T10") (pintype "bidirectional"))
      (node (ref "U10") (pin "8") (pinfunction "SDATA_8") (pintype "bidirectional"))
      (node (ref "U13") (pin "5") (pinfunction "DI_5") (pintype "bidirectional"))
      (node (ref "U3") (pin "36") (pinfunction "PB15-SPI2MOSI/TIM1CH3N_36") (pintype "bidirectional"))
    )
    (net (code "94") (name "SPI2NSS_FLASH") (class "Default")
      (node (ref "R13") (pin "P$1") (pinfunction "1_P$1") (pintype "passive"))
      (node (ref "U1") (pin "T3") (pinfunction "IO_L65N_CSO_B_2_T3") (pintype "bidirectional"))
      (node (ref "U13") (pin "1") (pinfunction "NCS_1") (pintype "input"))
      (node (ref "U3") (pin "33") (pinfunction "PB12-SPI2NSS/I2C2SMBAI/USART3CK/TIM1BKIN_33") (pintype "bidirectional"))
    )
    (net (code "95") (name "SPI2NSS_FPGA") (class "Default")
      (node (ref "U3") (pin "10") (pinfunction "PC2-ADC12_10") (pintype "bidirectional"))
    )
    (net (code "96") (name "SPI2NSS_MAX") (class "Default")
      (node (ref "U10") (pin "10") (pinfunction "~{CS}_10") (pintype "bidirectional"))
      (node (ref "U3") (pin "30") (pinfunction "PB11-I2C2SDA/USART3RX-TIM2CH4_30") (pintype "bidirectional"))
    )
    (net (code "97") (name "SPI2SCK") (class "Default")
      (node (ref "U1") (pin "R11") (pinfunction "IO_L1P_CCLK_2_R11") (pintype "bidirectional"))
      (node (ref "U10") (pin "9") (pinfunction "SCLK_9") (pintype "bidirectional"))
      (node (ref "U13") (pin "6") (pinfunction "CLK_6") (pintype "input"))
      (node (ref "U3") (pin "34") (pinfunction "PB13-SPI2SCK/USART3CTS/TIM1CH1N_34") (pintype "bidirectional"))
    )
    (net (code "98") (name "STM_CLK_IN") (class "Default")
      (node (ref "U1") (pin "P9") (pinfunction "IO_L14N_D12_2_P9") (pintype "bidirectional"))
      (node (ref "U3") (pin "5") (pinfunction "PD0-OSC_IN-CANRX_5") (pintype "input"))
    )
    (net (code "99") (name "TIM2CH1ETR") (class "Default")
      (node (ref "U1") (pin "C10") (pinfunction "IO_L37N_GCLK12_0_C10") (pintype "bidirectional"))
      (node (ref "U3") (pin "14") (pinfunction "PA0-WKUP/USART2CTS/ADC0/TIM2CH1ETR_14") (pintype "bidirectional"))
    )
    (net (code "100") (name "TIM2CH2") (class "Default")
      (node (ref "U1") (pin "A9") (pinfunction "IO_L34N_GCLK18_0_A9") (pintype "bidirectional"))
      (node (ref "U3") (pin "15") (pinfunction "PA1-USART2RTS/ADC1/TIM2CH2_15") (pintype "bidirectional"))
    )
    (net (code "101") (name "TIM2CH3") (class "Default")
      (node (ref "U1") (pin "A7") (pinfunction "IO_L6N_0_A7") (pintype "bidirectional"))
      (node (ref "U3") (pin "16") (pinfunction "PA2-USART2TX/ADC2/TIM2CH3_16") (pintype "bidirectional"))
    )
    (net (code "102") (name "TIM2CH4") (class "Default")
      (node (ref "U1") (pin "A5") (pinfunction "IO_L2N_0_A5") (pintype "bidirectional"))
      (node (ref "U3") (pin "17") (pinfunction "PA3-USART2RX/ADC3/TIM2CH4_17") (pintype "bidirectional"))
    )
    (net (code "103") (name "UART1_RX") (class "Default")
      (node (ref "U3") (pin "43") (pinfunction "PA10-USART1RX/TIM1CH3_43") (pintype "bidirectional"))
      (node (ref "X6") (pin "2") (pinfunction "2_2") (pintype "bidirectional"))
    )
    (net (code "104") (name "UART1_TX") (class "Default")
      (node (ref "U3") (pin "42") (pinfunction "PA9-USART1TX/TIM1CH2_42") (pintype "bidirectional"))
      (node (ref "X6") (pin "3") (pinfunction "3_3") (pintype "bidirectional"))
    )
    (net (code "105") (name "UART3_RX") (class "Default")
      (node (ref "U3") (pin "52") (pinfunction "PC11--USART3RX_52") (pintype "bidirectional"))
      (node (ref "X1") (pin "2") (pinfunction "2_2") (pintype "bidirectional"))
    )
    (net (code "106") (name "UART3_TX") (class "Default")
      (node (ref "U3") (pin "51") (pinfunction "PC10--USART3TX_51") (pintype "bidirectional"))
      (node (ref "X1") (pin "3") (pinfunction "3_3") (pintype "bidirectional"))
    )
    (net (code "107") (name "UART6_RX{slash}FTDI_ADBUS0") (class "Default")
      (node (ref "U1") (pin "H15") (pinfunction "IO_L37P_A7_M1A0_1_H15") (pintype "bidirectional"))
      (node (ref "U3") (pin "38") (pinfunction "PC7-TIM3CH2_38") (pintype "bidirectional"))
      (node (ref "U7") (pin "13") (pinfunction "AD0_13") (pintype "bidirectional"))
    )
    (net (code "108") (name "UART6_TX{slash}FTDI_ADBUS1") (class "Default")
      (node (ref "U1") (pin "G16") (pinfunction "IO_L36N_A8_M1BA1_1_G16") (pintype "bidirectional"))
      (node (ref "U3") (pin "37") (pinfunction "PC6-TIM3CH1_37") (pintype "bidirectional"))
      (node (ref "U7") (pin "14") (pinfunction "AD1_14") (pintype "bidirectional"))
    )
    (net (code "109") (name "USB_DM") (class "Default")
      (node (ref "J6") (pin "PIN_2") (pinfunction "2_PIN_2") (pintype "input"))
      (node (ref "U7") (pin "6") (pinfunction "DM_6") (pintype "bidirectional"))
    )
    (net (code "110") (name "USB_DP") (class "Default")
      (node (ref "J6") (pin "PIN_3") (pinfunction "3_PIN_3") (pintype "input"))
      (node (ref "U7") (pin "7") (pinfunction "DP_7") (pintype "bidirectional"))
    )
    (net (code "111") (name "V+") (class "Default")
      (node (ref "D1") (pin "2") (pinfunction "2_2") (pintype "bidirectional"))
      (node (ref "Q1") (pin "3") (pinfunction "D_3") (pintype "passive"))
      (node (ref "X1") (pin "5") (pinfunction "5_5") (pintype "bidirectional"))
      (node (ref "X3") (pin "12") (pinfunction "12_12") (pintype "bidirectional"))
      (node (ref "X6") (pin "5") (pinfunction "5_5") (pintype "bidirectional"))
    )
    (net (code "112") (name "VCC") (class "Default")
      (node (ref "C11") (pin "P$2") (pinfunction "2_P$2") (pintype "passive"))
      (node (ref "C37") (pin "P$1") (pinfunction "1_P$1") (pintype "passive"))
      (node (ref "C39") (pin "P$1") (pinfunction "1_P$1") (pintype "passive"))
      (node (ref "C40") (pin "P$1") (pinfunction "1_P$1") (pintype "passive"))
      (node (ref "C42") (pin "P$1") (pinfunction "1_P$1") (pintype "passive"))
      (node (ref "L2") (pin "P$2") (pinfunction "2_P$2") (pintype "passive"))
      (node (ref "R11") (pin "P$2") (pinfunction "2_P$2") (pintype "passive"))
      (node (ref "U10") (pin "11") (pinfunction "VCCVCO_11") (pintype "bidirectional"))
      (node (ref "U10") (pin "13") (pinfunction "VCCCP_13") (pintype "bidirectional"))
      (node (ref "U10") (pin "23") (pinfunction "VCCIF_23") (pintype "bidirectional"))
      (node (ref "U12") (pin "5") (pinfunction "VOUT_5") (pintype "bidirectional"))
    )
    (net (code "113") (name "VCCINT") (class "Default")
      (node (ref "C10") (pin "P$1") (pinfunction "1_P$1") (pintype "passive"))
      (node (ref "C17") (pin "P$1") (pinfunction "1_P$1") (pintype "passive"))
      (node (ref "C24") (pin "P$1") (pinfunction "1_P$1") (pintype "bidirectional"))
      (node (ref "C28") (pin "P$1") (pinfunction "1_P$1") (pintype "passive"))
      (node (ref "C29") (pin "P$1") (pinfunction "1_P$1") (pintype "passive"))
      (node (ref "C30") (pin "P$1") (pinfunction "1_P$1") (pintype "passive"))
      (node (ref "C31") (pin "P$1") (pinfunction "1_P$1") (pintype "passive"))
      (node (ref "C4") (pin "P$1") (pinfunction "1_P$1") (pintype "passive"))
      (node (ref "C43") (pin "P$1") (pinfunction "1_P$1") (pintype "passive"))
      (node (ref "C46") (pin "P$1") (pinfunction "1_P$1") (pintype "passive"))
      (node (ref "C5") (pin "P$1") (pinfunction "1_P$1") (pintype "passive"))
      (node (ref "C78") (pin "P$1") (pinfunction "1_P$1") (pintype "passive"))
      (node (ref "C80") (pin "P$1") (pinfunction "1_P$1") (pintype "passive"))
      (node (ref "C81") (pin "P$1") (pinfunction "1_P$1") (pintype "passive"))
      (node (ref "L14") (pin "2") (pinfunction "2_2") (pintype "bidirectional"))
      (node (ref "R64") (pin "P$2") (pinfunction "2_P$2") (pintype "passive"))
      (node (ref "U1") (pin "G7") (pinfunction "VCCINT_G7") (pintype "input"))
      (node (ref "U1") (pin "G9") (pinfunction "VCCINT_G9") (pintype "input"))
      (node (ref "U1") (pin "H10") (pinfunction "VCCINT_H10") (pintype "input"))
      (node (ref "U1") (pin "H8") (pinfunction "VCCINT_H8") (pintype "input"))
      (node (ref "U1") (pin "J7") (pinfunction "VCCINT_J7") (pintype "input"))
      (node (ref "U1") (pin "J9") (pinfunction "VCCINT_J9") (pintype "input"))
      (node (ref "U1") (pin "K10") (pinfunction "VCCINT_K10") (pintype "input"))
      (node (ref "U1") (pin "K8") (pinfunction "VCCINT_K8") (pintype "input"))
    )
    (net (code "114") (name "VCCIO") (class "Default")
      (node (ref "C1") (pin "P$2") (pinfunction "2_P$2") (pintype "passive"))
      (node (ref "C107") (pin "P$1") (pinfunction "1_P$1") (pintype "passive"))
      (node (ref "C21") (pin "P$1") (pinfunction "1_P$1") (pintype "bidirectional"))
      (node (ref "C22") (pin "P$1") (pinfunction "1_P$1") (pintype "passive"))
      (node (ref "C23") (pin "P$1") (pinfunction "1_P$1") (pintype "passive"))
      (node (ref "C25") (pin "P$1") (pinfunction "1_P$1") (pintype "bidirectional"))
      (node (ref "C26") (pin "P$1") (pinfunction "1_P$1") (pintype "bidirectional"))
      (node (ref "C27") (pin "P$1") (pinfunction "1_P$1") (pintype "passive"))
      (node (ref "C3") (pin "P$1") (pinfunction "1_P$1") (pintype "passive"))
      (node (ref "C33") (pin "P$2") (pinfunction "2_P$2") (pintype "passive"))
      (node (ref "C44") (pin "P$1") (pinfunction "1_P$1") (pintype "passive"))
      (node (ref "C45") (pin "1") (pinfunction "1_1") (pintype "passive"))
      (node (ref "C48") (pin "P$1") (pinfunction "1_P$1") (pintype "passive"))
      (node (ref "C50") (pin "P$2") (pinfunction "2_P$2") (pintype "passive"))
      (node (ref "C51") (pin "P$2") (pinfunction "2_P$2") (pintype "passive"))
      (node (ref "C52") (pin "P$1") (pinfunction "1_P$1") (pintype "passive"))
      (node (ref "C53") (pin "P$1") (pinfunction "1_P$1") (pintype "passive"))
      (node (ref "C54") (pin "P$1") (pinfunction "1_P$1") (pintype "passive"))
      (node (ref "C55") (pin "P$1") (pinfunction "1_P$1") (pintype "passive"))
      (node (ref "C56") (pin "P$1") (pinfunction "1_P$1") (pintype "passive"))
      (node (ref "C57") (pin "P$2") (pinfunction "2_P$2") (pintype "passive"))
      (node (ref "C58") (pin "P$1") (pinfunction "1_P$1") (pintype "passive"))
      (node (ref "C60") (pin "P$1") (pinfunction "1_P$1") (pintype "passive"))
      (node (ref "C61") (pin "P$1") (pinfunction "1_P$1") (pintype "passive"))
      (node (ref "C62") (pin "P$1") (pinfunction "1_P$1") (pintype "passive"))
      (node (ref "C63") (pin "P$1") (pinfunction "1_P$1") (pintype "passive"))
      (node (ref "C67") (pin "P$1") (pinfunction "1_P$1") (pintype "passive"))
      (node (ref "C69") (pin "1") (pinfunction "1_1") (pintype "passive"))
      (node (ref "C70") (pin "P$1") (pinfunction "1_P$1") (pintype "passive"))
      (node (ref "C71") (pin "P$1") (pinfunction "1_P$1") (pintype "passive"))
      (node (ref "C72") (pin "P$1") (pinfunction "1_P$1") (pintype "passive"))
      (node (ref "C73") (pin "P$1") (pinfunction "1_P$1") (pintype "passive"))
      (node (ref "C74") (pin "P$1") (pinfunction "1_P$1") (pintype "passive"))
      (node (ref "C76") (pin "P$1") (pinfunction "1_P$1") (pintype "passive"))
      (node (ref "C77") (pin "P$1") (pinfunction "1_P$1") (pintype "passive"))
      (node (ref "C8") (pin "P$1") (pinfunction "1_P$1") (pintype "passive"))
      (node (ref "C86") (pin "P$1") (pinfunction "1_P$1") (pintype "bidirectional"))
      (node (ref "C87") (pin "P$1") (pinfunction "1_P$1") (pintype "bidirectional"))
      (node (ref "C96") (pin "P$1") (pinfunction "1_P$1") (pintype "passive"))
      (node (ref "L10") (pin "P$1") (pinfunction "1_P$1") (pintype "passive"))
      (node (ref "L11") (pin "P$1") (pinfunction "1_P$1") (pintype "passive"))
      (node (ref "L13") (pin "1") (pinfunction "1_1") (pintype "bidirectional"))
      (node (ref "R12") (pin "P$2") (pinfunction "2_P$2") (pintype "passive"))
      (node (ref "R13") (pin "P$2") (pinfunction "2_P$2") (pintype "passive"))
      (node (ref "R15") (pin "P$1") (pinfunction "1_P$1") (pintype "passive"))
      (node (ref "R16") (pin "P$2") (pinfunction "2_P$2") (pintype "passive"))
      (node (ref "R17") (pin "P$1") (pinfunction "1_P$1") (pintype "passive"))
      (node (ref "R19") (pin "P$2") (pinfunction "2_P$2") (pintype "passive"))
      (node (ref "R28") (pin "P$1") (pinfunction "1_P$1") (pintype "passive"))
      (node (ref "R30") (pin "P$2") (pinfunction "2_P$2") (pintype "passive"))
      (node (ref "R34") (pin "P$2") (pinfunction "2_P$2") (pintype "passive"))
      (node (ref "R4") (pin "P$1") (pinfunction "1_P$1") (pintype "passive"))
      (node (ref "R5") (pin "P$1") (pinfunction "1_P$1") (pintype "passive"))
      (node (ref "R6") (pin "P$1") (pinfunction "1_P$1") (pintype "passive"))
      (node (ref "R61") (pin "P$2") (pinfunction "2_P$2") (pintype "passive"))
      (node (ref "U1") (pin "B13") (pinfunction "VCCO_0_B13") (pintype "input"))
      (node (ref "U1") (pin "B4") (pinfunction "VCCO_0_B4") (pintype "input"))
      (node (ref "U1") (pin "B9") (pinfunction "VCCO_0_B9") (pintype "input"))
      (node (ref "U1") (pin "D10") (pinfunction "VCCO_0_D10") (pintype "input"))
      (node (ref "U1") (pin "D15") (pinfunction "VCCO_1_D15") (pintype "input"))
      (node (ref "U1") (pin "D2") (pinfunction "VCCO_3_D2") (pintype "input"))
      (node (ref "U1") (pin "D7") (pinfunction "VCCO_0_D7") (pintype "input"))
      (node (ref "U1") (pin "E5") (pinfunction "VCCAUX_E5") (pintype "input"))
      (node (ref "U1") (pin "F11") (pinfunction "VCCAUX_F11") (pintype "input"))
      (node (ref "U1") (pin "F8") (pinfunction "VCCAUX_F8") (pintype "input"))
      (node (ref "U1") (pin "G10") (pinfunction "VCCAUX_G10") (pintype "input"))
      (node (ref "U1") (pin "G13") (pinfunction "VCCO_1_G13") (pintype "input"))
      (node (ref "U1") (pin "G4") (pinfunction "VCCO_3_G4") (pintype "input"))
      (node (ref "U1") (pin "H6") (pinfunction "VCCAUX_H6") (pintype "input"))
      (node (ref "U1") (pin "J10") (pinfunction "VCCAUX_J10") (pintype "input"))
      (node (ref "U1") (pin "J15") (pinfunction "VCCO_1_J15") (pintype "input"))
      (node (ref "U1") (pin "J2") (pinfunction "VCCO_3_J2") (pintype "input"))
      (node (ref "U1") (pin "K13") (pinfunction "VCCO_1_K13") (pintype "input"))
      (node (ref "U1") (pin "K4") (pinfunction "VCCO_3_K4") (pintype "input"))
      (node (ref "U1") (pin "L6") (pinfunction "VCCAUX_L6") (pintype "input"))
      (node (ref "U1") (pin "L9") (pinfunction "VCCAUX_L9") (pintype "input"))
      (node (ref "U1") (pin "N10") (pinfunction "VCCO_2_N10") (pintype "input"))
      (node (ref "U1") (pin "N15") (pinfunction "VCCO_1_N15") (pintype "input"))
      (node (ref "U1") (pin "N2") (pinfunction "VCCO_3_N2") (pintype "input"))
      (node (ref "U1") (pin "N7") (pinfunction "VCCO_2_N7") (pintype "input"))
      (node (ref "U1") (pin "R13") (pinfunction "VCCO_1_R13") (pintype "input"))
      (node (ref "U1") (pin "R4") (pinfunction "VCCO_2_R4") (pintype "input"))
      (node (ref "U1") (pin "R8") (pinfunction "VCCO_2_R8") (pintype "input"))
      (node (ref "U1") (pin "T11") (pinfunction "IO_L1N_M0_CMPMISO_2_T11") (pintype "bidirectional"))
      (node (ref "U10") (pin "14") (pinfunction "VCCD_14") (pintype "bidirectional"))
      (node (ref "U10") (pin "19") (pinfunction "VCCADC_19") (pintype "bidirectional"))
      (node (ref "U13") (pin "3") (pinfunction "NWP_3") (pintype "input"))
      (node (ref "U13") (pin "7") (pinfunction "NHOLD_7") (pintype "input"))
      (node (ref "U13") (pin "8") (pinfunction "VCC_8") (pintype "power_in"))
      (node (ref "U3") (pin "1") (pinfunction "VBAT_1") (pintype "power_in"))
      (node (ref "U3") (pin "13") (pinfunction "VDDA_13") (pintype "power_in"))
      (node (ref "U3") (pin "19") (pinfunction "VDD4_19") (pintype "bidirectional"))
      (node (ref "U3") (pin "32") (pinfunction "VDD1_32") (pintype "power_in"))
      (node (ref "U3") (pin "48") (pinfunction "VDD2_48") (pintype "power_in"))
      (node (ref "U3") (pin "64") (pinfunction "VDD3_64") (pintype "power_in"))
      (node (ref "U4") (pin "4") (pinfunction "VDD_4") (pintype "bidirectional"))
      (node (ref "U6") (pin "6") (pinfunction "VCC_6") (pintype "power_in"))
      (node (ref "U7") (pin "12") (pinfunction "VCCIO1_12") (pintype "power_in"))
      (node (ref "U7") (pin "24") (pinfunction "VCCIO2_24") (pintype "power_in"))
      (node (ref "U7") (pin "39") (pinfunction "VCCD_39") (pintype "bidirectional"))
      (node (ref "U7") (pin "40") (pinfunction "VREGIN_40") (pintype "power_in"))
      (node (ref "U7") (pin "46") (pinfunction "VCCIO3_46") (pintype "power_in"))
      (node (ref "X1") (pin "4") (pinfunction "4_4") (pintype "bidirectional"))
      (node (ref "X5") (pin "1") (pinfunction "1_1") (pintype "bidirectional"))
      (node (ref "X6") (pin "4") (pinfunction "4_4") (pintype "bidirectional"))
    )
    (net (code "115") (name "VDD") (class "Default")
      (node (ref "C2") (pin "P$1") (pinfunction "1_P$1") (pintype "passive"))
      (node (ref "C6") (pin "P$2") (pinfunction "2_P$2") (pintype "passive"))
      (node (ref "Q1") (pin "2") (pinfunction "S_2") (pintype "passive"))
      (node (ref "R1") (pin "P$2") (pinfunction "2_P$2") (pintype "passive"))
      (node (ref "R65") (pin "P$1") (pinfunction "1_P$1") (pintype "passive"))
      (node (ref "U2") (pin "2") (pinfunction "RUN/SS1_2") (pintype "bidirectional"))
      (node (ref "U2") (pin "3") (pinfunction "VIN_3") (pintype "bidirectional"))
      (node (ref "U2") (pin "6") (pinfunction "MODE/SYNC_6") (pintype "bidirectional"))
      (node (ref "U2") (pin "9") (pinfunction "RUN/SS2_9") (pintype "bidirectional"))
    )
    (net (code "116") (name "V_USB") (class "Default")
      (node (ref "D1") (pin "1") (pinfunction "1_1") (pintype "bidirectional"))
      (node (ref "J6") (pin "PIN_1") (pinfunction "1_PIN_1") (pintype "input"))
      (node (ref "R10") (pin "P$2") (pinfunction "2_P$2") (pintype "passive"))
      (node (ref "R8") (pin "P$2") (pinfunction "2_P$2") (pintype "passive"))
      (node (ref "R9") (pin "P$1") (pinfunction "1_P$1") (pintype "passive"))
    )
    (net (code "117") (name "unconnected-(J6-4-PadPIN_4)") (class "Default")
      (node (ref "J6") (pin "PIN_4") (pinfunction "4_PIN_4") (pintype "input"))
    )
    (net (code "118") (name "unconnected-(J6-S1-PadGND_LEFT)") (class "Default")
      (node (ref "J6") (pin "GND_LEFT") (pinfunction "S1_GND_LEFT") (pintype "passive"))
    )
    (net (code "119") (name "unconnected-(J6-S2-PadGND_RIGHT)") (class "Default")
      (node (ref "J6") (pin "GND_RIGHT") (pinfunction "S2_GND_RIGHT") (pintype "passive"))
    )
    (net (code "120") (name "unconnected-(J6-S3-PadGND_UP_LEFT)") (class "Default")
      (node (ref "J6") (pin "GND_UP_LEFT") (pinfunction "S3_GND_UP_LEFT") (pintype "passive"))
    )
    (net (code "121") (name "unconnected-(J6-S4-PadGND_UP_RIGHT)") (class "Default")
      (node (ref "J6") (pin "GND_UP_RIGHT") (pinfunction "S4_GND_UP_RIGHT") (pintype "passive"))
    )
    (net (code "122") (name "unconnected-(U1A-IO_L1N_VREF_0-PadA4)") (class "Default")
      (node (ref "U1") (pin "A4") (pinfunction "IO_L1N_VREF_0_A4") (pintype "bidirectional"))
    )
    (net (code "123") (name "unconnected-(U1A-IO_L2P_0-PadB5)") (class "Default")
      (node (ref "U1") (pin "B5") (pinfunction "IO_L2P_0_B5") (pintype "bidirectional"))
    )
    (net (code "124") (name "unconnected-(U1A-IO_L3N_0-PadC5)") (class "Default")
      (node (ref "U1") (pin "C5") (pinfunction "IO_L3N_0_C5") (pintype "bidirectional"))
    )
    (net (code "125") (name "unconnected-(U1A-IO_L3P_0-PadD5)") (class "Default")
      (node (ref "U1") (pin "D5") (pinfunction "IO_L3P_0_D5") (pintype "bidirectional"))
    )
    (net (code "126") (name "unconnected-(U1A-IO_L4N_0-PadA6)") (class "Default")
      (node (ref "U1") (pin "A6") (pinfunction "IO_L4N_0_A6") (pintype "bidirectional"))
    )
    (net (code "127") (name "unconnected-(U1A-IO_L4P_0-PadB6)") (class "Default")
      (node (ref "U1") (pin "B6") (pinfunction "IO_L4P_0_B6") (pintype "bidirectional"))
    )
    (net (code "128") (name "unconnected-(U1A-IO_L5N_0-PadE6)") (class "Default")
      (node (ref "U1") (pin "E6") (pinfunction "IO_L5N_0_E6") (pintype "bidirectional"))
    )
    (net (code "129") (name "unconnected-(U1A-IO_L5P_0-PadF7)") (class "Default")
      (node (ref "U1") (pin "F7") (pinfunction "IO_L5P_0_F7") (pintype "bidirectional"))
    )
    (net (code "130") (name "unconnected-(U1A-IO_L6P_0-PadC7)") (class "Default")
      (node (ref "U1") (pin "C7") (pinfunction "IO_L6P_0_C7") (pintype "bidirectional"))
    )
    (net (code "131") (name "unconnected-(U1A-IO_L7N_0-PadC6)") (class "Default")
      (node (ref "U1") (pin "C6") (pinfunction "IO_L7N_0_C6") (pintype "bidirectional"))
    )
    (net (code "132") (name "unconnected-(U1A-IO_L7P_0-PadD6)") (class "Default")
      (node (ref "U1") (pin "D6") (pinfunction "IO_L7P_0_D6") (pintype "bidirectional"))
    )
    (net (code "133") (name "unconnected-(U1A-IO_L33N_0-PadA8)") (class "Default")
      (node (ref "U1") (pin "A8") (pinfunction "IO_L33N_0_A8") (pintype "bidirectional"))
    )
    (net (code "134") (name "unconnected-(U1A-IO_L33P_0-PadB8)") (class "Default")
      (node (ref "U1") (pin "B8") (pinfunction "IO_L33P_0_B8") (pintype "bidirectional"))
    )
    (net (code "135") (name "unconnected-(U1A-IO_L34P_GCLK19_0-PadC9)") (class "Default")
      (node (ref "U1") (pin "C9") (pinfunction "IO_L34P_GCLK19_0_C9") (pintype "bidirectional"))
    )
    (net (code "136") (name "unconnected-(U1A-IO_L36N_GCLK14_0-PadE8)") (class "Default")
      (node (ref "U1") (pin "E8") (pinfunction "IO_L36N_GCLK14_0_E8") (pintype "bidirectional"))
    )
    (net (code "137") (name "unconnected-(U1A-IO_L36P_GCLK15_0-PadE7)") (class "Default")
      (node (ref "U1") (pin "E7") (pinfunction "IO_L36P_GCLK15_0_E7") (pintype "bidirectional"))
    )
    (net (code "138") (name "unconnected-(U1A-IO_L37P_GCLK13_0-PadE10)") (class "Default")
      (node (ref "U1") (pin "E10") (pinfunction "IO_L37P_GCLK13_0_E10") (pintype "bidirectional"))
    )
    (net (code "139") (name "unconnected-(U1A-IO_L38N_VREF_0-PadC8)") (class "Default")
      (node (ref "U1") (pin "C8") (pinfunction "IO_L38N_VREF_0_C8") (pintype "bidirectional"))
    )
    (net (code "140") (name "unconnected-(U1A-IO_L38P_0-PadD8)") (class "Default")
      (node (ref "U1") (pin "D8") (pinfunction "IO_L38P_0_D8") (pintype "bidirectional"))
    )
    (net (code "141") (name "unconnected-(U1A-IO_L39N_0-PadA11)") (class "Default")
      (node (ref "U1") (pin "A11") (pinfunction "IO_L39N_0_A11") (pintype "bidirectional"))
    )
    (net (code "142") (name "unconnected-(U1A-IO_L40N_0-PadD9)") (class "Default")
      (node (ref "U1") (pin "D9") (pinfunction "IO_L40N_0_D9") (pintype "bidirectional"))
    )
    (net (code "143") (name "unconnected-(U1A-IO_L40P_0-PadF9)") (class "Default")
      (node (ref "U1") (pin "F9") (pinfunction "IO_L40P_0_F9") (pintype "bidirectional"))
    )
    (net (code "144") (name "unconnected-(U1A-IO_L62P_0-PadB12)") (class "Default")
      (node (ref "U1") (pin "B12") (pinfunction "IO_L62P_0_B12") (pintype "bidirectional"))
    )
    (net (code "145") (name "unconnected-(U1A-IO_L63N_SCP6_0-PadA13)") (class "Default")
      (node (ref "U1") (pin "A13") (pinfunction "IO_L63N_SCP6_0_A13") (pintype "bidirectional"))
    )
    (net (code "146") (name "unconnected-(U1A-IO_L63P_SCP7_0-PadC13)") (class "Default")
      (node (ref "U1") (pin "C13") (pinfunction "IO_L63P_SCP7_0_C13") (pintype "bidirectional"))
    )
    (net (code "147") (name "unconnected-(U1A-IO_L64N_SCP4_0-PadE11)") (class "Default")
      (node (ref "U1") (pin "E11") (pinfunction "IO_L64N_SCP4_0_E11") (pintype "bidirectional"))
    )
    (net (code "148") (name "unconnected-(U1A-IO_L64P_SCP5_0-PadF10)") (class "Default")
      (node (ref "U1") (pin "F10") (pinfunction "IO_L64P_SCP5_0_F10") (pintype "bidirectional"))
    )
    (net (code "149") (name "unconnected-(U1A-IO_L65N_SCP2_0-PadA14)") (class "Default")
      (node (ref "U1") (pin "A14") (pinfunction "IO_L65N_SCP2_0_A14") (pintype "bidirectional"))
    )
    (net (code "150") (name "unconnected-(U1A-IO_L65P_SCP3_0-PadB14)") (class "Default")
      (node (ref "U1") (pin "B14") (pinfunction "IO_L65P_SCP3_0_B14") (pintype "bidirectional"))
    )
    (net (code "151") (name "unconnected-(U1A-IO_L66N_SCP0_0-PadD12)") (class "Default")
      (node (ref "U1") (pin "D12") (pinfunction "IO_L66N_SCP0_0_D12") (pintype "bidirectional"))
    )
    (net (code "152") (name "unconnected-(U1A-IO_L66P_SCP1_0-PadD11)") (class "Default")
      (node (ref "U1") (pin "D11") (pinfunction "IO_L66P_SCP1_0_D11") (pintype "bidirectional"))
    )
    (net (code "153") (name "unconnected-(U1B-IO_L1N_A24_VREF_1-PadE12)") (class "Default")
      (node (ref "U1") (pin "E12") (pinfunction "IO_L1N_A24_VREF_1_E12") (pintype "bidirectional"))
    )
    (net (code "154") (name "unconnected-(U1B-IO_L1P_A25_1-PadE13)") (class "Default")
      (node (ref "U1") (pin "E13") (pinfunction "IO_L1P_A25_1_E13") (pintype "bidirectional"))
    )
    (net (code "155") (name "unconnected-(U1B-IO_L29N_A22_M1A14_1-PadB16)") (class "Default")
      (node (ref "U1") (pin "B16") (pinfunction "IO_L29N_A22_M1A14_1_B16") (pintype "bidirectional"))
    )
    (net (code "156") (name "unconnected-(U1B-IO_L29P_A23_M1A13_1-PadB15)") (class "Default")
      (node (ref "U1") (pin "B15") (pinfunction "IO_L29P_A23_M1A13_1_B15") (pintype "bidirectional"))
    )
    (net (code "157") (name "unconnected-(U1B-IO_L30N_A20_M1A11_1-PadG11)") (class "Default")
      (node (ref "U1") (pin "G11") (pinfunction "IO_L30N_A20_M1A11_1_G11") (pintype "bidirectional"))
    )
    (net (code "158") (name "unconnected-(U1B-IO_L30P_A21_M1RESET_1-PadF12)") (class "Default")
      (node (ref "U1") (pin "F12") (pinfunction "IO_L30P_A21_M1RESET_1_F12") (pintype "bidirectional"))
    )
    (net (code "159") (name "unconnected-(U1B-IO_L31N_A18_M1A12_1-PadD16)") (class "Default")
      (node (ref "U1") (pin "D16") (pinfunction "IO_L31N_A18_M1A12_1_D16") (pintype "bidirectional"))
    )
    (net (code "160") (name "unconnected-(U1B-IO_L31P_A19_M1CKE_1-PadD14)") (class "Default")
      (node (ref "U1") (pin "D14") (pinfunction "IO_L31P_A19_M1CKE_1_D14") (pintype "bidirectional"))
    )
    (net (code "161") (name "unconnected-(U1B-IO_L32N_A16_M1A9_1-PadF14)") (class "Default")
      (node (ref "U1") (pin "F14") (pinfunction "IO_L32N_A16_M1A9_1_F14") (pintype "bidirectional"))
    )
    (net (code "162") (name "unconnected-(U1B-IO_L32P_A17_M1A8_1-PadF13)") (class "Default")
      (node (ref "U1") (pin "F13") (pinfunction "IO_L32P_A17_M1A8_1_F13") (pintype "bidirectional"))
    )
    (net (code "163") (name "unconnected-(U1B-IO_L33N_A14_M1A4_1-PadC16)") (class "Default")
      (node (ref "U1") (pin "C16") (pinfunction "IO_L33N_A14_M1A4_1_C16") (pintype "bidirectional"))
    )
    (net (code "164") (name "unconnected-(U1B-IO_L33P_A15_M1A10_1-PadC15)") (class "Default")
      (node (ref "U1") (pin "C15") (pinfunction "IO_L33P_A15_M1A10_1_C15") (pintype "bidirectional"))
    )
    (net (code "165") (name "unconnected-(U1B-IO_L36P_A9_M1BA0_1-PadG14)") (class "Default")
      (node (ref "U1") (pin "G14") (pinfunction "IO_L36P_A9_M1BA0_1_G14") (pintype "bidirectional"))
    )
    (net (code "166") (name "unconnected-(U1B-IO_L37N_A6_M1A1_1-PadH16)") (class "Default")
      (node (ref "U1") (pin "H16") (pinfunction "IO_L37N_A6_M1A1_1_H16") (pintype "bidirectional"))
    )
    (net (code "167") (name "unconnected-(U1B-IO_L38N_A4_M1CLKN_1-PadH11)") (class "Default")
      (node (ref "U1") (pin "H11") (pinfunction "IO_L38N_A4_M1CLKN_1_H11") (pintype "bidirectional"))
    )
    (net (code "168") (name "unconnected-(U1B-IO_L38P_A5_M1CLK_1-PadG12)") (class "Default")
      (node (ref "U1") (pin "G12") (pinfunction "IO_L38P_A5_M1CLK_1_G12") (pintype "bidirectional"))
    )
    (net (code "169") (name "unconnected-(U1B-IO_L39N_M1ODT_1-PadH14)") (class "Default")
      (node (ref "U1") (pin "H14") (pinfunction "IO_L39N_M1ODT_1_H14") (pintype "bidirectional"))
    )
    (net (code "170") (name "unconnected-(U1B-IO_L39P_M1A3_1-PadH13)") (class "Default")
      (node (ref "U1") (pin "H13") (pinfunction "IO_L39P_M1A3_1_H13") (pintype "bidirectional"))
    )
    (net (code "171") (name "unconnected-(U1B-IO_L40N_GCLK10_M1A6_1-PadJ12)") (class "Default")
      (node (ref "U1") (pin "J12") (pinfunction "IO_L40N_GCLK10_M1A6_1_J12") (pintype "bidirectional"))
    )
    (net (code "172") (name "unconnected-(U1B-IO_L40P_GCLK11_M1A5_1-PadJ11)") (class "Default")
      (node (ref "U1") (pin "J11") (pinfunction "IO_L40P_GCLK11_M1A5_1_J11") (pintype "bidirectional"))
    )
    (net (code "173") (name "unconnected-(U1B-IO_L41P_GCLK9_IRDY1_M1RASN_1-PadJ13)") (class "Default")
      (node (ref "U1") (pin "J13") (pinfunction "IO_L41P_GCLK9_IRDY1_M1RASN_1_J13") (pintype "bidirectional"))
    )
    (net (code "174") (name "unconnected-(U1B-IO_L42N_GCLK6_TRDY1_M1LDM_1-PadK11)") (class "Default")
      (node (ref "U1") (pin "K11") (pinfunction "IO_L42N_GCLK6_TRDY1_M1LDM_1_K11") (pintype "bidirectional"))
    )
    (net (code "175") (name "unconnected-(U1B-IO_L42P_GCLK7_M1UDM_1-PadK12)") (class "Default")
      (node (ref "U1") (pin "K12") (pinfunction "IO_L42P_GCLK7_M1UDM_1_K12") (pintype "bidirectional"))
    )
    (net (code "176") (name "unconnected-(U1B-IO_L43N_GCLK4_M1DQ5_1-PadJ16)") (class "Default")
      (node (ref "U1") (pin "J16") (pinfunction "IO_L43N_GCLK4_M1DQ5_1_J16") (pintype "bidirectional"))
    )
    (net (code "177") (name "unconnected-(U1B-IO_L48P_HDC_M1DQ8_1-PadP15)") (class "Default")
      (node (ref "U1") (pin "P15") (pinfunction "IO_L48P_HDC_M1DQ8_1_P15") (pintype "bidirectional"))
    )
    (net (code "178") (name "unconnected-(U1B-IO_L49N_M1DQ11_1-PadR16)") (class "Default")
      (node (ref "U1") (pin "R16") (pinfunction "IO_L49N_M1DQ11_1_R16") (pintype "bidirectional"))
    )
    (net (code "179") (name "unconnected-(U1B-IO_L50P_M1UDQS_1-PadR14)") (class "Default")
      (node (ref "U1") (pin "R14") (pinfunction "IO_L50P_M1UDQS_1_R14") (pintype "bidirectional"))
    )
    (net (code "180") (name "unconnected-(U1B-IO_L51N_M1DQ13_1-PadT13)") (class "Default")
      (node (ref "U1") (pin "T13") (pinfunction "IO_L51N_M1DQ13_1_T13") (pintype "bidirectional"))
    )
    (net (code "181") (name "unconnected-(U1B-IO_L51P_M1DQ12_1-PadT14)") (class "Default")
      (node (ref "U1") (pin "T14") (pinfunction "IO_L51P_M1DQ12_1_T14") (pintype "bidirectional"))
    )
    (net (code "182") (name "unconnected-(U1B-IO_L52N_M1DQ15_1-PadT12)") (class "Default")
      (node (ref "U1") (pin "T12") (pinfunction "IO_L52N_M1DQ15_1_T12") (pintype "bidirectional"))
    )
    (net (code "183") (name "unconnected-(U1B-IO_L52P_M1DQ14_1-PadR12)") (class "Default")
      (node (ref "U1") (pin "R12") (pinfunction "IO_L52P_M1DQ14_1_R12") (pintype "bidirectional"))
    )
    (net (code "184") (name "unconnected-(U1B-IO_L53N_VREF_1-PadL13)") (class "Default")
      (node (ref "U1") (pin "L13") (pinfunction "IO_L53N_VREF_1_L13") (pintype "bidirectional"))
    )
    (net (code "185") (name "unconnected-(U1B-IO_L53P_1-PadL12)") (class "Default")
      (node (ref "U1") (pin "L12") (pinfunction "IO_L53P_1_L12") (pintype "bidirectional"))
    )
    (net (code "186") (name "unconnected-(U1B-IO_L74P_AWAKE_1-PadM13)") (class "Default")
      (node (ref "U1") (pin "M13") (pinfunction "IO_L74P_AWAKE_1_M13") (pintype "bidirectional"))
    )
    (net (code "187") (name "unconnected-(U1C-CMPCS_B_2-PadL11)") (class "Default")
      (node (ref "U1") (pin "L11") (pinfunction "CMPCS_B_2_L11") (pintype "bidirectional"))
    )
    (net (code "188") (name "unconnected-(U1C-IO_L2N_CMPMOSI_2-PadM11)") (class "Default")
      (node (ref "U1") (pin "M11") (pinfunction "IO_L2N_CMPMOSI_2_M11") (pintype "bidirectional"))
    )
    (net (code "189") (name "unconnected-(U1C-IO_L2P_CMPCLK_2-PadM12)") (class "Default")
      (node (ref "U1") (pin "M12") (pinfunction "IO_L2P_CMPCLK_2_M12") (pintype "bidirectional"))
    )
    (net (code "190") (name "unconnected-(U1C-IO_L12N_D2_MISO3_2-PadP12)") (class "Default")
      (node (ref "U1") (pin "P12") (pinfunction "IO_L12N_D2_MISO3_2_P12") (pintype "bidirectional"))
    )
    (net (code "191") (name "unconnected-(U1C-IO_L12P_D1_MISO2_2-PadN12)") (class "Default")
      (node (ref "U1") (pin "N12") (pinfunction "IO_L12P_D1_MISO2_2_N12") (pintype "bidirectional"))
    )
    (net (code "192") (name "unconnected-(U1C-IO_L13N_D10_2-PadP11)") (class "Default")
      (node (ref "U1") (pin "P11") (pinfunction "IO_L13N_D10_2_P11") (pintype "bidirectional"))
    )
    (net (code "193") (name "unconnected-(U1C-IO_L14P_D11_2-PadN9)") (class "Default")
      (node (ref "U1") (pin "N9") (pinfunction "IO_L14P_D11_2_N9") (pintype "bidirectional"))
    )
    (net (code "194") (name "unconnected-(U1C-IO_L16N_VREF_2-PadM10)") (class "Default")
      (node (ref "U1") (pin "M10") (pinfunction "IO_L16N_VREF_2_M10") (pintype "bidirectional"))
    )
    (net (code "195") (name "unconnected-(U1C-IO_L16P_2-PadL10)") (class "Default")
      (node (ref "U1") (pin "L10") (pinfunction "IO_L16P_2_L10") (pintype "bidirectional"))
    )
    (net (code "196") (name "unconnected-(U1C-IO_L23N_2-PadT9)") (class "Default")
      (node (ref "U1") (pin "T9") (pinfunction "IO_L23N_2_T9") (pintype "bidirectional"))
    )
    (net (code "197") (name "unconnected-(U1C-IO_L23P_2-PadR9)") (class "Default")
      (node (ref "U1") (pin "R9") (pinfunction "IO_L23P_2_R9") (pintype "bidirectional"))
    )
    (net (code "198") (name "unconnected-(U1C-IO_L29N_GCLK2_2-PadN8)") (class "Default")
      (node (ref "U1") (pin "N8") (pinfunction "IO_L29N_GCLK2_2_N8") (pintype "bidirectional"))
    )
    (net (code "199") (name "unconnected-(U1C-IO_L29P_GCLK3_2-PadM9)") (class "Default")
      (node (ref "U1") (pin "M9") (pinfunction "IO_L29P_GCLK3_2_M9") (pintype "bidirectional"))
    )
    (net (code "200") (name "unconnected-(U1C-IO_L30N_GCLK0_USERCCLK_2-PadT8)") (class "Default")
      (node (ref "U1") (pin "T8") (pinfunction "IO_L30N_GCLK0_USERCCLK_2_T8") (pintype "bidirectional"))
    )
    (net (code "201") (name "unconnected-(U1C-IO_L30P_GCLK1_D13_2-PadP8)") (class "Default")
      (node (ref "U1") (pin "P8") (pinfunction "IO_L30P_GCLK1_D13_2_P8") (pintype "bidirectional"))
    )
    (net (code "202") (name "unconnected-(U1C-IO_L31N_GCLK30_D15_2-PadM7)") (class "Default")
      (node (ref "U1") (pin "M7") (pinfunction "IO_L31N_GCLK30_D15_2_M7") (pintype "bidirectional"))
    )
    (net (code "203") (name "unconnected-(U1C-IO_L31P_GCLK31_D14_2-PadP7)") (class "Default")
      (node (ref "U1") (pin "P7") (pinfunction "IO_L31P_GCLK31_D14_2_P7") (pintype "bidirectional"))
    )
    (net (code "204") (name "unconnected-(U1C-IO_L32N_GCLK28_2-PadT7)") (class "Default")
      (node (ref "U1") (pin "T7") (pinfunction "IO_L32N_GCLK28_2_T7") (pintype "bidirectional"))
    )
    (net (code "205") (name "unconnected-(U1C-IO_L32P_GCLK29_2-PadR7)") (class "Default")
      (node (ref "U1") (pin "R7") (pinfunction "IO_L32P_GCLK29_2_R7") (pintype "bidirectional"))
    )
    (net (code "206") (name "unconnected-(U1C-IO_L47N_2-PadT6)") (class "Default")
      (node (ref "U1") (pin "T6") (pinfunction "IO_L47N_2_T6") (pintype "bidirectional"))
    )
    (net (code "207") (name "unconnected-(U1C-IO_L47P_2-PadP6)") (class "Default")
      (node (ref "U1") (pin "P6") (pinfunction "IO_L47P_2_P6") (pintype "bidirectional"))
    )
    (net (code "208") (name "unconnected-(U1C-IO_L48N_RDWR_B_VREF_2-PadT5)") (class "Default")
      (node (ref "U1") (pin "T5") (pinfunction "IO_L48N_RDWR_B_VREF_2_T5") (pintype "bidirectional"))
    )
    (net (code "209") (name "unconnected-(U1C-IO_L48P_D7_2-PadR5)") (class "Default")
      (node (ref "U1") (pin "R5") (pinfunction "IO_L48P_D7_2_R5") (pintype "bidirectional"))
    )
    (net (code "210") (name "unconnected-(U1C-IO_L49N_D4_2-PadP5)") (class "Default")
      (node (ref "U1") (pin "P5") (pinfunction "IO_L49N_D4_2_P5") (pintype "bidirectional"))
    )
    (net (code "211") (name "unconnected-(U1C-IO_L49P_D3_2-PadN5)") (class "Default")
      (node (ref "U1") (pin "N5") (pinfunction "IO_L49P_D3_2_N5") (pintype "bidirectional"))
    )
    (net (code "212") (name "unconnected-(U1C-IO_L62N_D6_2-PadL7)") (class "Default")
      (node (ref "U1") (pin "L7") (pinfunction "IO_L62N_D6_2_L7") (pintype "bidirectional"))
    )
    (net (code "213") (name "unconnected-(U1C-IO_L62P_D5_2-PadL8)") (class "Default")
      (node (ref "U1") (pin "L8") (pinfunction "IO_L62P_D5_2_L8") (pintype "bidirectional"))
    )
    (net (code "214") (name "unconnected-(U1C-IO_L63N_2-PadT4)") (class "Default")
      (node (ref "U1") (pin "T4") (pinfunction "IO_L63N_2_T4") (pintype "bidirectional"))
    )
    (net (code "215") (name "unconnected-(U1C-IO_L63P_2-PadP4)") (class "Default")
      (node (ref "U1") (pin "P4") (pinfunction "IO_L63P_2_P4") (pintype "bidirectional"))
    )
    (net (code "216") (name "unconnected-(U1C-IO_L64N_D9_2-PadN6)") (class "Default")
      (node (ref "U1") (pin "N6") (pinfunction "IO_L64N_D9_2_N6") (pintype "bidirectional"))
    )
    (net (code "217") (name "unconnected-(U1C-IO_L64P_D8_2-PadM6)") (class "Default")
      (node (ref "U1") (pin "M6") (pinfunction "IO_L64P_D8_2_M6") (pintype "bidirectional"))
    )
    (net (code "218") (name "unconnected-(U1D-IO_L1N_VREF_3-PadM3)") (class "Default")
      (node (ref "U1") (pin "M3") (pinfunction "IO_L1N_VREF_3_M3") (pintype "bidirectional"))
    )
    (net (code "219") (name "unconnected-(U1D-IO_L1P_3-PadM4)") (class "Default")
      (node (ref "U1") (pin "M4") (pinfunction "IO_L1P_3_M4") (pintype "bidirectional"))
    )
    (net (code "220") (name "unconnected-(U1D-IO_L2N_3-PadN4)") (class "Default")
      (node (ref "U1") (pin "N4") (pinfunction "IO_L2N_3_N4") (pintype "bidirectional"))
    )
    (net (code "221") (name "unconnected-(U1D-IO_L2P_3-PadM5)") (class "Default")
      (node (ref "U1") (pin "M5") (pinfunction "IO_L2P_3_M5") (pintype "bidirectional"))
    )
    (net (code "222") (name "unconnected-(U1D-IO_L32P_M3DQ14_3-PadR2)") (class "Default")
      (node (ref "U1") (pin "R2") (pinfunction "IO_L32P_M3DQ14_3_R2") (pintype "bidirectional"))
    )
    (net (code "223") (name "unconnected-(U1D-IO_L33N_M3DQ13_3-PadP1)") (class "Default")
      (node (ref "U1") (pin "P1") (pinfunction "IO_L33N_M3DQ13_3_P1") (pintype "bidirectional"))
    )
    (net (code "224") (name "unconnected-(U1D-IO_L33P_M3DQ12_3-PadP2)") (class "Default")
      (node (ref "U1") (pin "P2") (pinfunction "IO_L33P_M3DQ12_3_P2") (pintype "bidirectional"))
    )
    (net (code "225") (name "unconnected-(U1D-IO_L34P_M3UDQS_3-PadN3)") (class "Default")
      (node (ref "U1") (pin "N3") (pinfunction "IO_L34P_M3UDQS_3_N3") (pintype "bidirectional"))
    )
    (net (code "226") (name "unconnected-(U1D-IO_L35P_M3DQ10_3-PadM2)") (class "Default")
      (node (ref "U1") (pin "M2") (pinfunction "IO_L35P_M3DQ10_3_M2") (pintype "bidirectional"))
    )
    (net (code "227") (name "unconnected-(U1D-IO_L36P_M3DQ8_3-PadL3)") (class "Default")
      (node (ref "U1") (pin "L3") (pinfunction "IO_L36P_M3DQ8_3_L3") (pintype "bidirectional"))
    )
    (net (code "228") (name "unconnected-(U1D-IO_L37N_M3DQ1_3-PadK1)") (class "Default")
      (node (ref "U1") (pin "K1") (pinfunction "IO_L37N_M3DQ1_3_K1") (pintype "bidirectional"))
    )
    (net (code "229") (name "unconnected-(U1D-IO_L37P_M3DQ0_3-PadK2)") (class "Default")
      (node (ref "U1") (pin "K2") (pinfunction "IO_L37P_M3DQ0_3_K2") (pintype "bidirectional"))
    )
    (net (code "230") (name "unconnected-(U1D-IO_L38P_M3DQ2_3-PadJ3)") (class "Default")
      (node (ref "U1") (pin "J3") (pinfunction "IO_L38P_M3DQ2_3_J3") (pintype "bidirectional"))
    )
    (net (code "231") (name "unconnected-(U1D-IO_L39N_M3LDQSN_3-PadH1)") (class "Default")
      (node (ref "U1") (pin "H1") (pinfunction "IO_L39N_M3LDQSN_3_H1") (pintype "bidirectional"))
    )
    (net (code "232") (name "unconnected-(U1D-IO_L39P_M3LDQS_3-PadH2)") (class "Default")
      (node (ref "U1") (pin "H2") (pinfunction "IO_L39P_M3LDQS_3_H2") (pintype "bidirectional"))
    )
    (net (code "233") (name "unconnected-(U1D-IO_L40N_M3DQ7_3-PadG1)") (class "Default")
      (node (ref "U1") (pin "G1") (pinfunction "IO_L40N_M3DQ7_3_G1") (pintype "bidirectional"))
    )
    (net (code "234") (name "unconnected-(U1D-IO_L40P_M3DQ6_3-PadG3)") (class "Default")
      (node (ref "U1") (pin "G3") (pinfunction "IO_L40P_M3DQ6_3_G3") (pintype "bidirectional"))
    )
    (net (code "235") (name "unconnected-(U1D-IO_L41P_GCLK27_M3DQ4_3-PadF2)") (class "Default")
      (node (ref "U1") (pin "F2") (pinfunction "IO_L41P_GCLK27_M3DQ4_3_F2") (pintype "bidirectional"))
    )
    (net (code "236") (name "unconnected-(U1D-IO_L42N_GCLK24_M3LDM_3-PadJ4)") (class "Default")
      (node (ref "U1") (pin "J4") (pinfunction "IO_L42N_GCLK24_M3LDM_3_J4") (pintype "bidirectional"))
    )
    (net (code "237") (name "unconnected-(U1D-IO_L42P_GCLK25_TRDY2_M3UDM_3-PadK3)") (class "Default")
      (node (ref "U1") (pin "K3") (pinfunction "IO_L42P_GCLK25_TRDY2_M3UDM_3_K3") (pintype "bidirectional"))
    )
    (net (code "238") (name "unconnected-(U1D-IO_L43N_GCLK22_IRDY2_M3CASN_3-PadH5)") (class "Default")
      (node (ref "U1") (pin "H5") (pinfunction "IO_L43N_GCLK22_IRDY2_M3CASN_3_H5") (pintype "bidirectional"))
    )
    (net (code "239") (name "unconnected-(U1D-IO_L43P_GCLK23_M3RASN_3-PadJ6)") (class "Default")
      (node (ref "U1") (pin "J6") (pinfunction "IO_L43P_GCLK23_M3RASN_3_J6") (pintype "bidirectional"))
    )
    (net (code "240") (name "unconnected-(U1D-IO_L44P_GCLK21_M3A5_3-PadH4)") (class "Default")
      (node (ref "U1") (pin "H4") (pinfunction "IO_L44P_GCLK21_M3A5_3_H4") (pintype "bidirectional"))
    )
    (net (code "241") (name "unconnected-(U1D-IO_L45N_M3ODT_3-PadL5)") (class "Default")
      (node (ref "U1") (pin "L5") (pinfunction "IO_L45N_M3ODT_3_L5") (pintype "bidirectional"))
    )
    (net (code "242") (name "unconnected-(U1D-IO_L45P_M3A3_3-PadL4)") (class "Default")
      (node (ref "U1") (pin "L4") (pinfunction "IO_L45P_M3A3_3_L4") (pintype "bidirectional"))
    )
    (net (code "243") (name "unconnected-(U1D-IO_L46P_M3CLK_3-PadE2)") (class "Default")
      (node (ref "U1") (pin "E2") (pinfunction "IO_L46P_M3CLK_3_E2") (pintype "bidirectional"))
    )
    (net (code "244") (name "unconnected-(U1D-IO_L47N_M3A1_3-PadK6)") (class "Default")
      (node (ref "U1") (pin "K6") (pinfunction "IO_L47N_M3A1_3_K6") (pintype "bidirectional"))
    )
    (net (code "245") (name "unconnected-(U1D-IO_L47P_M3A0_3-PadK5)") (class "Default")
      (node (ref "U1") (pin "K5") (pinfunction "IO_L47P_M3A0_3_K5") (pintype "bidirectional"))
    )
    (net (code "246") (name "unconnected-(U1D-IO_L48N_M3BA1_3-PadC2)") (class "Default")
      (node (ref "U1") (pin "C2") (pinfunction "IO_L48N_M3BA1_3_C2") (pintype "bidirectional"))
    )
    (net (code "247") (name "unconnected-(U1D-IO_L48P_M3BA0_3-PadC3)") (class "Default")
      (node (ref "U1") (pin "C3") (pinfunction "IO_L48P_M3BA0_3_C3") (pintype "bidirectional"))
    )
    (net (code "248") (name "unconnected-(U1D-IO_L49P_M3A7_3-PadD3)") (class "Default")
      (node (ref "U1") (pin "D3") (pinfunction "IO_L49P_M3A7_3_D3") (pintype "bidirectional"))
    )
    (net (code "249") (name "unconnected-(U1D-IO_L50N_M3BA2_3-PadB1)") (class "Default")
      (node (ref "U1") (pin "B1") (pinfunction "IO_L50N_M3BA2_3_B1") (pintype "bidirectional"))
    )
    (net (code "250") (name "unconnected-(U1D-IO_L51N_M3A4_3-PadG5)") (class "Default")
      (node (ref "U1") (pin "G5") (pinfunction "IO_L51N_M3A4_3_G5") (pintype "bidirectional"))
    )
    (net (code "251") (name "unconnected-(U1D-IO_L51P_M3A10_3-PadG6)") (class "Default")
      (node (ref "U1") (pin "G6") (pinfunction "IO_L51P_M3A10_3_G6") (pintype "bidirectional"))
    )
    (net (code "252") (name "unconnected-(U1D-IO_L52N_M3A9_3-PadA2)") (class "Default")
      (node (ref "U1") (pin "A2") (pinfunction "IO_L52N_M3A9_3_A2") (pintype "bidirectional"))
    )
    (net (code "253") (name "unconnected-(U1D-IO_L52P_M3A8_3-PadB2)") (class "Default")
      (node (ref "U1") (pin "B2") (pinfunction "IO_L52P_M3A8_3_B2") (pintype "bidirectional"))
    )
    (net (code "254") (name "unconnected-(U1D-IO_L53N_M3A12_3-PadF3)") (class "Default")
      (node (ref "U1") (pin "F3") (pinfunction "IO_L53N_M3A12_3_F3") (pintype "bidirectional"))
    )
    (net (code "255") (name "unconnected-(U1D-IO_L53P_M3CKE_3-PadF4)") (class "Default")
      (node (ref "U1") (pin "F4") (pinfunction "IO_L53P_M3CKE_3_F4") (pintype "bidirectional"))
    )
    (net (code "256") (name "unconnected-(U1D-IO_L54N_M3A11_3-PadE3)") (class "Default")
      (node (ref "U1") (pin "E3") (pinfunction "IO_L54N_M3A11_3_E3") (pintype "bidirectional"))
    )
    (net (code "257") (name "unconnected-(U1D-IO_L54P_M3RESET_3-PadE4)") (class "Default")
      (node (ref "U1") (pin "E4") (pinfunction "IO_L54P_M3RESET_3_E4") (pintype "bidirectional"))
    )
    (net (code "258") (name "unconnected-(U1D-IO_L55N_M3A14_3-PadF5)") (class "Default")
      (node (ref "U1") (pin "F5") (pinfunction "IO_L55N_M3A14_3_F5") (pintype "bidirectional"))
    )
    (net (code "259") (name "unconnected-(U1D-IO_L55P_M3A13_3-PadF6)") (class "Default")
      (node (ref "U1") (pin "F6") (pinfunction "IO_L55P_M3A13_3_F6") (pintype "bidirectional"))
    )
    (net (code "260") (name "unconnected-(U1D-IO_L83N_VREF_3-PadA3)") (class "Default")
      (node (ref "U1") (pin "A3") (pinfunction "IO_L83N_VREF_3_A3") (pintype "bidirectional"))
    )
    (net (code "261") (name "unconnected-(U1D-IO_L83P_3-PadB3)") (class "Default")
      (node (ref "U1") (pin "B3") (pinfunction "IO_L83P_3_B3") (pintype "bidirectional"))
    )
    (net (code "262") (name "unconnected-(U3-PA11-USART1CTS{slash}CANRX{slash}USBDM{slash}TIM1CH4-Pad44)") (class "Default")
      (node (ref "U3") (pin "44") (pinfunction "PA11-USART1CTS/CANRX/USBDM/TIM1CH4_44") (pintype "bidirectional"))
    )
    (net (code "263") (name "unconnected-(U3-PA12-USART1RTS{slash}CANTX{slash}USBDP{slash}TIM1ETR-Pad45)") (class "Default")
      (node (ref "U3") (pin "45") (pinfunction "PA12-USART1RTS/CANTX/USBDP/TIM1ETR_45") (pintype "bidirectional"))
    )
    (net (code "264") (name "unconnected-(U3-PB2{slash}BOOT1-Pad28)") (class "Default")
      (node (ref "U3") (pin "28") (pinfunction "PB2/BOOT1_28") (pintype "bidirectional"))
    )
    (net (code "265") (name "unconnected-(U3-PB4{slash}JNTRST--TIM3CH1{slash}SPI1MISO-Pad56)") (class "Default")
      (node (ref "U3") (pin "56") (pinfunction "PB4/JNTRST--TIM3CH1/SPI1MISO_56") (pintype "bidirectional"))
    )
    (net (code "266") (name "unconnected-(U3-PB5-I2C1SMBAI-TIM3CH2{slash}SPI1MOSI-Pad57)") (class "Default")
      (node (ref "U3") (pin "57") (pinfunction "PB5-I2C1SMBAI-TIM3CH2/SPI1MOSI_57") (pintype "bidirectional"))
    )
    (net (code "267") (name "unconnected-(U3-PB6-I2C1SCL{slash}TIM4CH1-USART1TX-Pad58)") (class "Default")
      (node (ref "U3") (pin "58") (pinfunction "PB6-I2C1SCL/TIM4CH1-USART1TX_58") (pintype "bidirectional"))
    )
    (net (code "268") (name "unconnected-(U3-PB7-I2C1SDA{slash}TIM4CH2-USART1RX-Pad59)") (class "Default")
      (node (ref "U3") (pin "59") (pinfunction "PB7-I2C1SDA/TIM4CH2-USART1RX_59") (pintype "bidirectional"))
    )
    (net (code "269") (name "unconnected-(U3-PC8-TIM3CH3-Pad39)") (class "Default")
      (node (ref "U3") (pin "39") (pinfunction "PC8-TIM3CH3_39") (pintype "bidirectional"))
    )
    (net (code "270") (name "unconnected-(U3-PC9-TIM3CH4-Pad40)") (class "Default")
      (node (ref "U3") (pin "40") (pinfunction "PC9-TIM3CH4_40") (pintype "bidirectional"))
    )
    (net (code "271") (name "unconnected-(U3-PC13-TAMPER-RTC-Pad2)") (class "Default")
      (node (ref "U3") (pin "2") (pinfunction "PC13-TAMPER-RTC_2") (pintype "bidirectional"))
    )
    (net (code "272") (name "unconnected-(U3-PC14-OSC32_IN-Pad3)") (class "Default")
      (node (ref "U3") (pin "3") (pinfunction "PC14-OSC32_IN_3") (pintype "bidirectional"))
    )
    (net (code "273") (name "unconnected-(U3-PC15-OSC32_OUT-Pad4)") (class "Default")
      (node (ref "U3") (pin "4") (pinfunction "PC15-OSC32_OUT_4") (pintype "bidirectional"))
    )
    (net (code "274") (name "unconnected-(U3-PD1-OSC_OUT-CANTX-Pad6)") (class "Default")
      (node (ref "U3") (pin "6") (pinfunction "PD1-OSC_OUT-CANTX_6") (pintype "output"))
    )
    (net (code "275") (name "unconnected-(U3-PD2-TIM3ETR-Pad54)") (class "Default")
      (node (ref "U3") (pin "54") (pinfunction "PD2-TIM3ETR_54") (pintype "bidirectional"))
    )
    (net (code "276") (name "unconnected-(U7-AC8-Pad32)") (class "Default")
      (node (ref "U7") (pin "32") (pinfunction "AC8_32") (pintype "bidirectional"))
    )
    (net (code "277") (name "unconnected-(U7-AC9-Pad33)") (class "Default")
      (node (ref "U7") (pin "33") (pinfunction "AC9_33") (pintype "bidirectional"))
    )
    (net (code "278") (name "unconnected-(U10C-NC1-Pad22)") (class "Default")
      (node (ref "U10") (pin "22") (pinfunction "NC1_22") (pintype "bidirectional"))
    )
    (net (code "279") (name "unconnected-(U10C-NC2-Pad28)") (class "Default")
      (node (ref "U10") (pin "28") (pinfunction "NC2_28") (pintype "bidirectional"))
    )
    (net (code "280") (name "unconnected-(U12-NC-Pad4)") (class "Default")
      (node (ref "U12") (pin "4") (pinfunction "NC_4") (pintype "bidirectional"))
    )
  )
)
